# schematic.net
KiCad netlist of a schematic drawn in Altium Designer
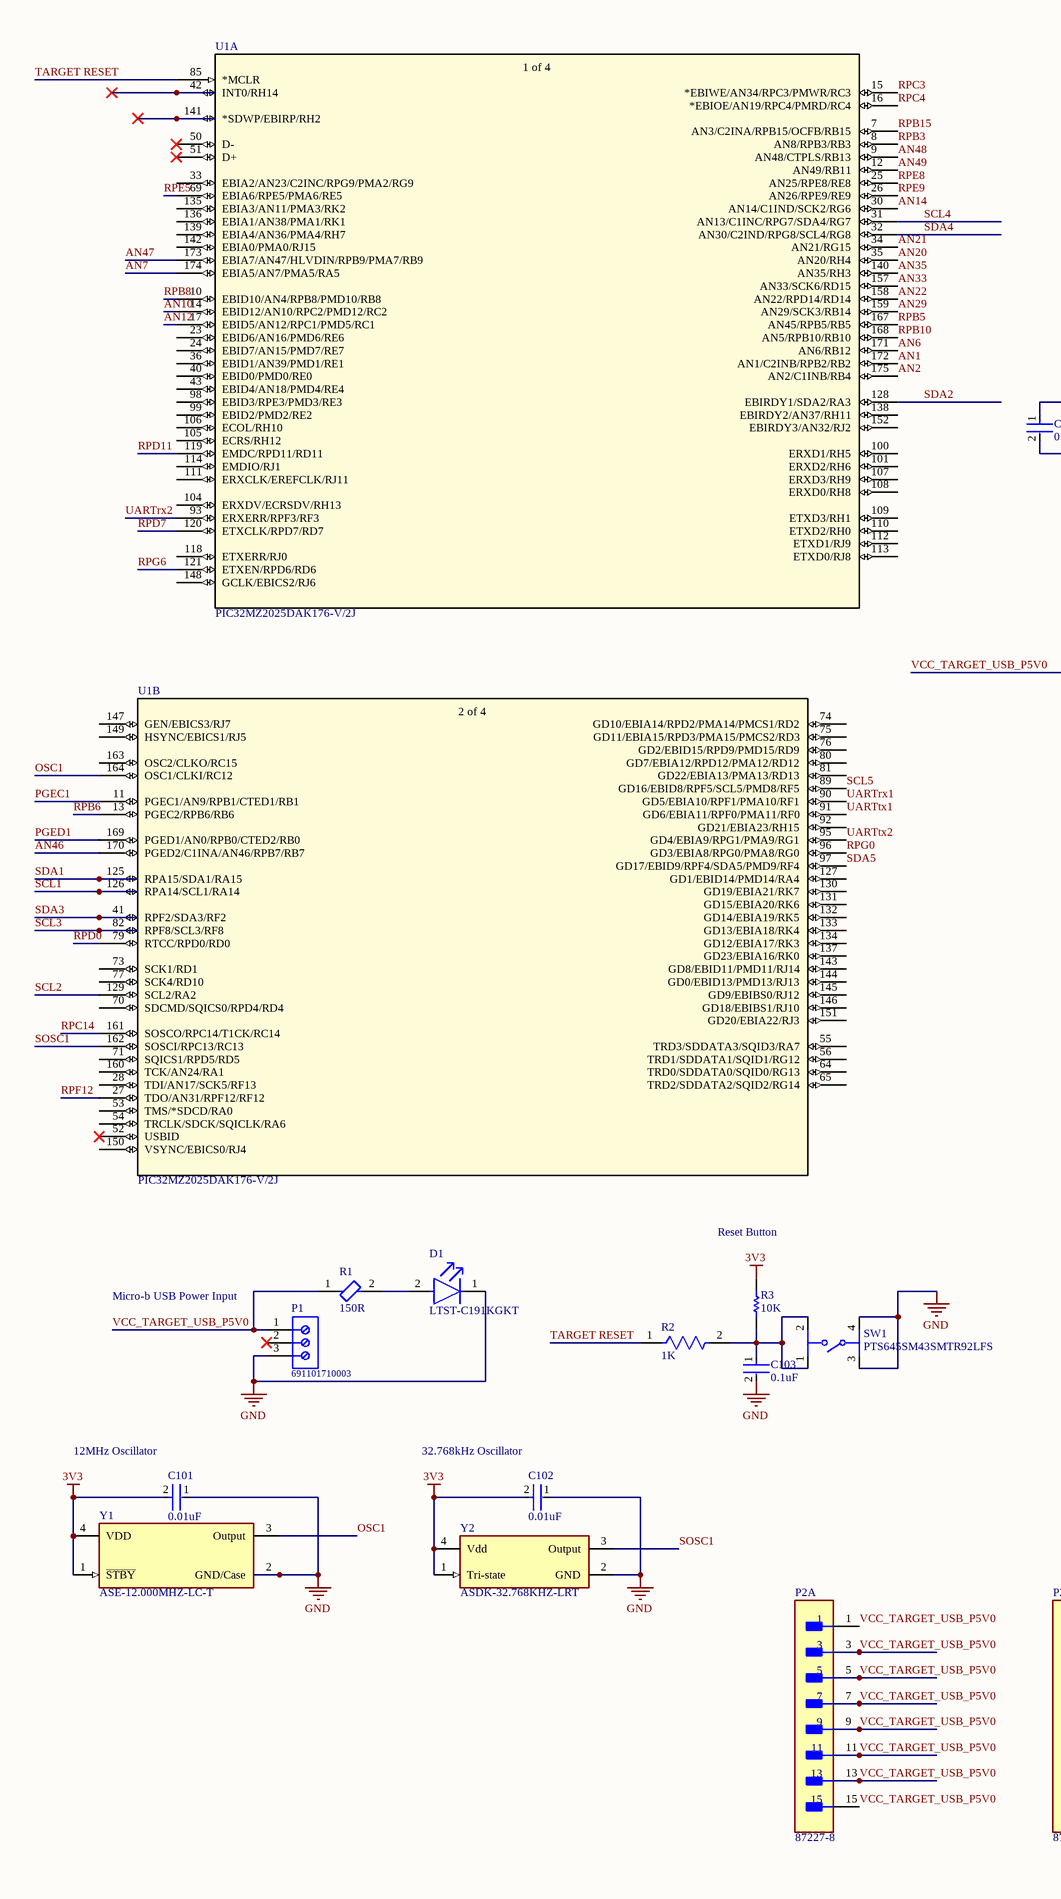
[diagram p0: schematic.SchDoc, left]
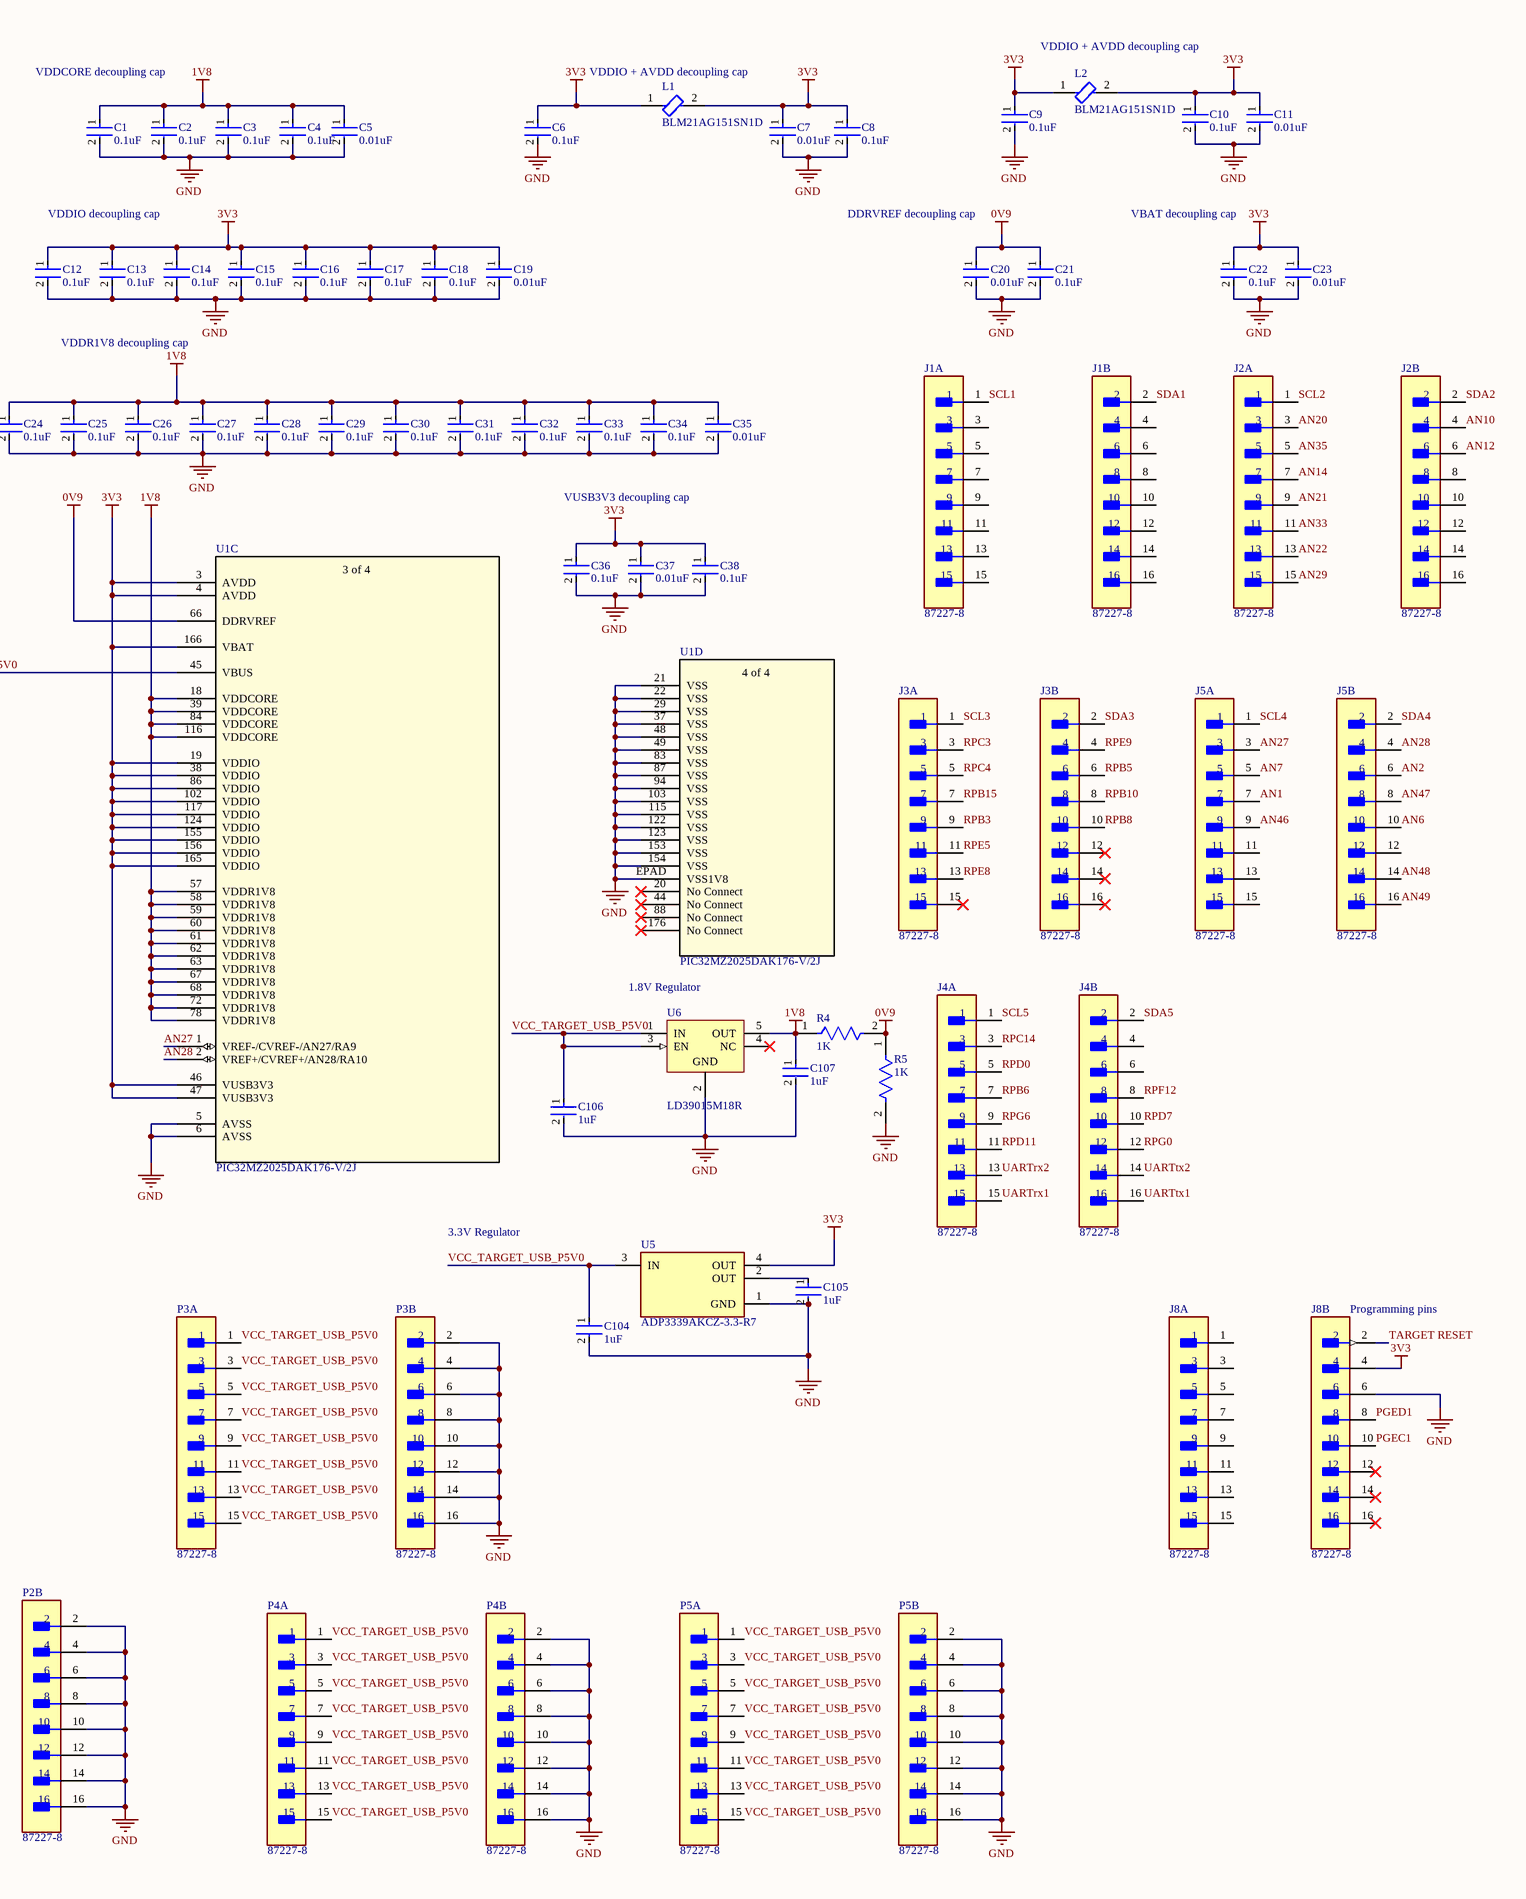
[diagram p1: schematic.SchDoc, right]

(export (version "E")
  (design (tool "Eeschema 10.0.6"))
  (components
    (comp (ref "C1")
      (value "0.1uF")
      (footprint "FP-CGA2B-MFG")
      (description "Cap Ceramic 100nF 50V X7R 10% Pad SMD 0402 +125°C Automotive T/R")
      (fields (field (name "VOLTAGE") "50V") (field (name "TOLERANCE") "10%"))
      (libsource (lib "Altium Content Vault") (part "b4654b650e69147ec39a6b967a45e02"))
    )
    (comp (ref "C2")
      (value "0.1uF")
      (footprint "FP-CGA2B-MFG")
      (description "Cap Ceramic 100nF 50V X7R 10% Pad SMD 0402 +125°C Automotive T/R")
      (fields (field (name "VOLTAGE") "50V") (field (name "TOLERANCE") "10%"))
      (libsource (lib "Altium Content Vault") (part "b4654b650e69147ec39a6b967a45e02"))
    )
    (comp (ref "C3")
      (value "0.1uF")
      (footprint "FP-CGA2B-MFG")
      (description "Cap Ceramic 100nF 50V X7R 10% Pad SMD 0402 +125°C Automotive T/R")
      (fields (field (name "VOLTAGE") "50V") (field (name "TOLERANCE") "10%"))
      (libsource (lib "Altium Content Vault") (part "b4654b650e69147ec39a6b967a45e02"))
    )
    (comp (ref "C4")
      (value "0.1uF")
      (footprint "FP-CGA2B-MFG")
      (description "Cap Ceramic 100nF 50V X7R 10% Pad SMD 0402 +125°C Automotive T/R")
      (fields (field (name "VOLTAGE") "50V") (field (name "TOLERANCE") "10%"))
      (libsource (lib "Altium Content Vault") (part "b4654b650e69147ec39a6b967a45e02"))
    )
    (comp (ref "C5")
      (value "0.01uF")
      (footprint "FP-C1005-050-0_05-IPC_B")
      (description "Multilayer Ceramic Capacitors 10nF ±20% 50V X5R SMD 0402")
      (fields (field (name "TOLERANCE") "20%"))
      (libsource (lib "Altium Content Vault") (part "b4654b650e69147ec39a6b967a45e02"))
    )
    (comp (ref "C6")
      (value "0.1uF")
      (footprint "FP-CGA2B-MFG")
      (description "Cap Ceramic 100nF 50V X7R 10% Pad SMD 0402 +125°C Automotive T/R")
      (fields (field (name "VOLTAGE") "50V") (field (name "TOLERANCE") "10%"))
      (libsource (lib "Altium Content Vault") (part "b4654b650e69147ec39a6b967a45e02"))
    )
    (comp (ref "C7")
      (value "0.01uF")
      (footprint "FP-C1005-050-0_05-IPC_B")
      (description "Multilayer Ceramic Capacitors 10nF ±20% 50V X5R SMD 0402")
      (fields (field (name "TOLERANCE") "20%"))
      (libsource (lib "Altium Content Vault") (part "b4654b650e69147ec39a6b967a45e02"))
    )
    (comp (ref "C8")
      (value "0.1uF")
      (footprint "FP-CGA2B-MFG")
      (description "Cap Ceramic 100nF 50V X7R 10% Pad SMD 0402 +125°C Automotive T/R")
      (fields (field (name "VOLTAGE") "50V") (field (name "TOLERANCE") "10%"))
      (libsource (lib "Altium Content Vault") (part "b4654b650e69147ec39a6b967a45e02"))
    )
    (comp (ref "C9")
      (value "0.1uF")
      (footprint "FP-CGA2B-MFG")
      (description "Cap Ceramic 100nF 50V X7R 10% Pad SMD 0402 +125°C Automotive T/R")
      (fields (field (name "VOLTAGE") "50V") (field (name "TOLERANCE") "10%"))
      (libsource (lib "Altium Content Vault") (part "b4654b650e69147ec39a6b967a45e02"))
    )
    (comp (ref "C10")
      (value "0.1uF")
      (footprint "FP-CGA2B-MFG")
      (description "Cap Ceramic 100nF 50V X7R 10% Pad SMD 0402 +125°C Automotive T/R")
      (fields (field (name "VOLTAGE") "50V") (field (name "TOLERANCE") "10%"))
      (libsource (lib "Altium Content Vault") (part "b4654b650e69147ec39a6b967a45e02"))
    )
    (comp (ref "C11")
      (value "0.01uF")
      (footprint "FP-C1005-050-0_05-IPC_B")
      (description "Multilayer Ceramic Capacitors 10nF ±20% 50V X5R SMD 0402")
      (fields (field (name "TOLERANCE") "20%"))
      (libsource (lib "Altium Content Vault") (part "b4654b650e69147ec39a6b967a45e02"))
    )
    (comp (ref "C12")
      (value "0.1uF")
      (footprint "FP-CGA2B-MFG")
      (description "Cap Ceramic 100nF 50V X7R 10% Pad SMD 0402 +125°C Automotive T/R")
      (fields (field (name "VOLTAGE") "50V") (field (name "TOLERANCE") "10%"))
      (libsource (lib "Altium Content Vault") (part "b4654b650e69147ec39a6b967a45e02"))
    )
    (comp (ref "C13")
      (value "0.1uF")
      (footprint "FP-CGA2B-MFG")
      (description "Cap Ceramic 100nF 50V X7R 10% Pad SMD 0402 +125°C Automotive T/R")
      (fields (field (name "VOLTAGE") "50V") (field (name "TOLERANCE") "10%"))
      (libsource (lib "Altium Content Vault") (part "b4654b650e69147ec39a6b967a45e02"))
    )
    (comp (ref "C14")
      (value "0.1uF")
      (footprint "FP-CGA2B-MFG")
      (description "Cap Ceramic 100nF 50V X7R 10% Pad SMD 0402 +125°C Automotive T/R")
      (fields (field (name "VOLTAGE") "50V") (field (name "TOLERANCE") "10%"))
      (libsource (lib "Altium Content Vault") (part "b4654b650e69147ec39a6b967a45e02"))
    )
    (comp (ref "C15")
      (value "0.1uF")
      (footprint "FP-CGA2B-MFG")
      (description "Cap Ceramic 100nF 50V X7R 10% Pad SMD 0402 +125°C Automotive T/R")
      (fields (field (name "VOLTAGE") "50V") (field (name "TOLERANCE") "10%"))
      (libsource (lib "Altium Content Vault") (part "b4654b650e69147ec39a6b967a45e02"))
    )
    (comp (ref "C16")
      (value "0.1uF")
      (footprint "FP-CGA2B-MFG")
      (description "Cap Ceramic 100nF 50V X7R 10% Pad SMD 0402 +125°C Automotive T/R")
      (fields (field (name "VOLTAGE") "50V") (field (name "TOLERANCE") "10%"))
      (libsource (lib "Altium Content Vault") (part "b4654b650e69147ec39a6b967a45e02"))
    )
    (comp (ref "C17")
      (value "0.1uF")
      (footprint "FP-CGA2B-MFG")
      (description "Cap Ceramic 100nF 50V X7R 10% Pad SMD 0402 +125°C Automotive T/R")
      (fields (field (name "VOLTAGE") "50V") (field (name "TOLERANCE") "10%"))
      (libsource (lib "Altium Content Vault") (part "b4654b650e69147ec39a6b967a45e02"))
    )
    (comp (ref "C18")
      (value "0.1uF")
      (footprint "FP-CGA2B-MFG")
      (description "Cap Ceramic 100nF 50V X7R 10% Pad SMD 0402 +125°C Automotive T/R")
      (fields (field (name "VOLTAGE") "50V") (field (name "TOLERANCE") "10%"))
      (libsource (lib "Altium Content Vault") (part "b4654b650e69147ec39a6b967a45e02"))
    )
    (comp (ref "C19")
      (value "0.01uF")
      (footprint "FP-C1005-050-0_05-IPC_B")
      (description "Multilayer Ceramic Capacitors 10nF ±20% 50V X5R SMD 0402")
      (fields (field (name "TOLERANCE") "20%"))
      (libsource (lib "Altium Content Vault") (part "b4654b650e69147ec39a6b967a45e02"))
    )
    (comp (ref "C20")
      (value "0.01uF")
      (footprint "FP-C1005-050-0_05-IPC_B")
      (description "Multilayer Ceramic Capacitors 10nF ±20% 50V X5R SMD 0402")
      (fields (field (name "TOLERANCE") "20%"))
      (libsource (lib "Altium Content Vault") (part "b4654b650e69147ec39a6b967a45e02"))
    )
    (comp (ref "C21")
      (value "0.1uF")
      (footprint "FP-CGA2B-MFG")
      (description "Cap Ceramic 100nF 50V X7R 10% Pad SMD 0402 +125°C Automotive T/R")
      (fields (field (name "VOLTAGE") "50V") (field (name "TOLERANCE") "10%"))
      (libsource (lib "Altium Content Vault") (part "b4654b650e69147ec39a6b967a45e02"))
    )
    (comp (ref "C22")
      (value "0.1uF")
      (footprint "FP-CGA2B-MFG")
      (description "Cap Ceramic 100nF 50V X7R 10% Pad SMD 0402 +125°C Automotive T/R")
      (fields (field (name "VOLTAGE") "50V") (field (name "TOLERANCE") "10%"))
      (libsource (lib "Altium Content Vault") (part "b4654b650e69147ec39a6b967a45e02"))
    )
    (comp (ref "C23")
      (value "0.01uF")
      (footprint "FP-C1005-050-0_05-IPC_B")
      (description "Multilayer Ceramic Capacitors 10nF ±20% 50V X5R SMD 0402")
      (fields (field (name "TOLERANCE") "20%"))
      (libsource (lib "Altium Content Vault") (part "b4654b650e69147ec39a6b967a45e02"))
    )
    (comp (ref "C24")
      (value "0.1uF")
      (footprint "FP-CGA2B-MFG")
      (description "Cap Ceramic 100nF 50V X7R 10% Pad SMD 0402 +125°C Automotive T/R")
      (fields (field (name "VOLTAGE") "50V") (field (name "TOLERANCE") "10%"))
      (libsource (lib "Altium Content Vault") (part "b4654b650e69147ec39a6b967a45e02"))
    )
    (comp (ref "C25")
      (value "0.1uF")
      (footprint "FP-CGA2B-MFG")
      (description "Cap Ceramic 100nF 50V X7R 10% Pad SMD 0402 +125°C Automotive T/R")
      (fields (field (name "VOLTAGE") "50V") (field (name "TOLERANCE") "10%"))
      (libsource (lib "Altium Content Vault") (part "b4654b650e69147ec39a6b967a45e02"))
    )
    (comp (ref "C26")
      (value "0.1uF")
      (footprint "FP-CGA2B-MFG")
      (description "Cap Ceramic 100nF 50V X7R 10% Pad SMD 0402 +125°C Automotive T/R")
      (fields (field (name "VOLTAGE") "50V") (field (name "TOLERANCE") "10%"))
      (libsource (lib "Altium Content Vault") (part "b4654b650e69147ec39a6b967a45e02"))
    )
    (comp (ref "C27")
      (value "0.1uF")
      (footprint "FP-CGA2B-MFG")
      (description "Cap Ceramic 100nF 50V X7R 10% Pad SMD 0402 +125°C Automotive T/R")
      (fields (field (name "VOLTAGE") "50V") (field (name "TOLERANCE") "10%"))
      (libsource (lib "Altium Content Vault") (part "b4654b650e69147ec39a6b967a45e02"))
    )
    (comp (ref "C28")
      (value "0.1uF")
      (footprint "FP-CGA2B-MFG")
      (description "Cap Ceramic 100nF 50V X7R 10% Pad SMD 0402 +125°C Automotive T/R")
      (fields (field (name "VOLTAGE") "50V") (field (name "TOLERANCE") "10%"))
      (libsource (lib "Altium Content Vault") (part "b4654b650e69147ec39a6b967a45e02"))
    )
    (comp (ref "C29")
      (value "0.1uF")
      (footprint "FP-CGA2B-MFG")
      (description "Cap Ceramic 100nF 50V X7R 10% Pad SMD 0402 +125°C Automotive T/R")
      (fields (field (name "VOLTAGE") "50V") (field (name "TOLERANCE") "10%"))
      (libsource (lib "Altium Content Vault") (part "b4654b650e69147ec39a6b967a45e02"))
    )
    (comp (ref "C30")
      (value "0.1uF")
      (footprint "FP-CGA2B-MFG")
      (description "Cap Ceramic 100nF 50V X7R 10% Pad SMD 0402 +125°C Automotive T/R")
      (fields (field (name "VOLTAGE") "50V") (field (name "TOLERANCE") "10%"))
      (libsource (lib "Altium Content Vault") (part "b4654b650e69147ec39a6b967a45e02"))
    )
    (comp (ref "C31")
      (value "0.1uF")
      (footprint "FP-CGA2B-MFG")
      (description "Cap Ceramic 100nF 50V X7R 10% Pad SMD 0402 +125°C Automotive T/R")
      (fields (field (name "VOLTAGE") "50V") (field (name "TOLERANCE") "10%"))
      (libsource (lib "Altium Content Vault") (part "b4654b650e69147ec39a6b967a45e02"))
    )
    (comp (ref "C32")
      (value "0.1uF")
      (footprint "FP-CGA2B-MFG")
      (description "Cap Ceramic 100nF 50V X7R 10% Pad SMD 0402 +125°C Automotive T/R")
      (fields (field (name "VOLTAGE") "50V") (field (name "TOLERANCE") "10%"))
      (libsource (lib "Altium Content Vault") (part "b4654b650e69147ec39a6b967a45e02"))
    )
    (comp (ref "C33")
      (value "0.1uF")
      (footprint "FP-CGA2B-MFG")
      (description "Cap Ceramic 100nF 50V X7R 10% Pad SMD 0402 +125°C Automotive T/R")
      (fields (field (name "VOLTAGE") "50V") (field (name "TOLERANCE") "10%"))
      (libsource (lib "Altium Content Vault") (part "b4654b650e69147ec39a6b967a45e02"))
    )
    (comp (ref "C34")
      (value "0.1uF")
      (footprint "FP-CGA2B-MFG")
      (description "Cap Ceramic 100nF 50V X7R 10% Pad SMD 0402 +125°C Automotive T/R")
      (fields (field (name "VOLTAGE") "50V") (field (name "TOLERANCE") "10%"))
      (libsource (lib "Altium Content Vault") (part "b4654b650e69147ec39a6b967a45e02"))
    )
    (comp (ref "C35")
      (value "0.01uF")
      (footprint "FP-C1005-050-0_05-IPC_B")
      (description "Multilayer Ceramic Capacitors 10nF ±20% 50V X5R SMD 0402")
      (fields (field (name "TOLERANCE") "20%"))
      (libsource (lib "Altium Content Vault") (part "b4654b650e69147ec39a6b967a45e02"))
    )
    (comp (ref "C36")
      (value "0.1uF")
      (footprint "FP-CGA2B-MFG")
      (description "Cap Ceramic 100nF 50V X7R 10% Pad SMD 0402 +125°C Automotive T/R")
      (fields (field (name "VOLTAGE") "50V") (field (name "TOLERANCE") "10%"))
      (libsource (lib "Altium Content Vault") (part "b4654b650e69147ec39a6b967a45e02"))
    )
    (comp (ref "C37")
      (value "0.01uF")
      (footprint "FP-C1005-050-0_05-IPC_B")
      (description "Multilayer Ceramic Capacitors 10nF ±20% 50V X5R SMD 0402")
      (fields (field (name "TOLERANCE") "20%"))
      (libsource (lib "Altium Content Vault") (part "b4654b650e69147ec39a6b967a45e02"))
    )
    (comp (ref "C38")
      (value "0.1uF")
      (footprint "FP-CGA2B-MFG")
      (description "Cap Ceramic 100nF 50V X7R 10% Pad SMD 0402 +125°C Automotive T/R")
      (fields (field (name "VOLTAGE") "50V") (field (name "TOLERANCE") "10%"))
      (libsource (lib "Altium Content Vault") (part "b4654b650e69147ec39a6b967a45e02"))
    )
    (comp (ref "C101")
      (value "0.01uF")
      (footprint "FP-C1608-080-0_1-MFG")
      (description "Multilayer Ceramic Capacitors 10nF ±10% 50V X7R SMD 0603")
      (fields (field (name "VOLTAGE") "50V") (field (name "TOLERANCE") "10%"))
      (libsource (lib "Altium Content Vault") (part "236180d848d6139a670b325ea6854c9"))
    )
    (comp (ref "C102")
      (value "0.01uF")
      (footprint "FP-C1608-080-0_1-MFG")
      (description "Multilayer Ceramic Capacitors 10nF ±10% 50V X7R SMD 0603")
      (fields (field (name "VOLTAGE") "50V") (field (name "TOLERANCE") "10%"))
      (libsource (lib "Altium Content Vault") (part "236180d848d6139a670b325ea6854c9"))
    )
    (comp (ref "C103")
      (value "0.1uF")
      (footprint "FP-CGA3E-0_3-0_1-IPC_A")
      (description "Cap Ceramic 100nF 50V X7R 10% Pad SMD 0603 +125°C Automotive T/R")
      (fields (field (name "TOLERANCE") "10%") (field (name "VOLTAGE") "50V"))
      (libsource (lib "Altium Content Vault") (part "b4654b650e69147ec39a6b967a45e02"))
    )
    (comp (ref "C104")
      (value "1uF")
      (footprint "FP-0603-L_1_6_0_1-W_0_8_0-IPC_B")
      (description "None")
      (fields (field (name "TOLERANCE") "10%"))
      (libsource (lib "Altium Content Vault") (part "02cd4be3c70576c341d710602a673aa"))
    )
    (comp (ref "C105")
      (value "1uF")
      (footprint "FP-0603-L_1_6_0_1-W_0_8_0-IPC_B")
      (description "None")
      (fields (field (name "TOLERANCE") "10%"))
      (libsource (lib "Altium Content Vault") (part "02cd4be3c70576c341d710602a673aa"))
    )
    (comp (ref "C106")
      (value "1uF")
      (footprint "FP-0603-L_1_6_0_1-W_0_8_0-IPC_B")
      (description "None")
      (fields (field (name "TOLERANCE") "10%"))
      (libsource (lib "Altium Content Vault") (part "02cd4be3c70576c341d710602a673aa"))
    )
    (comp (ref "C107")
      (value "1uF")
      (footprint "FP-0603-L_1_6_0_1-W_0_8_0-IPC_B")
      (description "None")
      (fields (field (name "TOLERANCE") "10%"))
      (libsource (lib "Altium Content Vault") (part "02cd4be3c70576c341d710602a673aa"))
    )
    (comp (ref "D1")
      (value "LTST-C191KGKT")
      (footprint "FP-LTST-C191KGKT-MFG")
      (description "LED GREEN CLEAR SMD")
      (libsource (lib "Altium Content Vault") (part "8706943c75ba83719d021d2fdc84c58"))
    )
    (comp (ref "J1")
      (value "87227-8")
      (footprint "FP-87227-8-MFG")
      (description "CONN HEADER VERT 16POS 2.54MM")
      (fields
        (field (name "MANUFACTURER") "TE Connectivity")
        (field (name "OCTOPART") "https://octopart.com/87227-8-te+connectivity-39407754")
      )
      (libsource (lib "Altium Content Vault") (part "4b6d22b45e2f925f038cba5d936fbcc"))
    )
    (comp (ref "J2")
      (value "87227-8")
      (footprint "FP-87227-8-MFG")
      (description "CONN HEADER VERT 16POS 2.54MM")
      (fields
        (field (name "MANUFACTURER") "TE Connectivity")
        (field (name "OCTOPART") "https://octopart.com/87227-8-te+connectivity-39407754")
      )
      (libsource (lib "Altium Content Vault") (part "4b6d22b45e2f925f038cba5d936fbcc"))
    )
    (comp (ref "J3")
      (value "87227-8")
      (footprint "FP-87227-8-MFG")
      (description "CONN HEADER VERT 16POS 2.54MM")
      (fields
        (field (name "MANUFACTURER") "TE Connectivity")
        (field (name "OCTOPART") "https://octopart.com/87227-8-te+connectivity-39407754")
      )
      (libsource (lib "Altium Content Vault") (part "4b6d22b45e2f925f038cba5d936fbcc"))
    )
    (comp (ref "J4")
      (value "87227-8")
      (footprint "FP-87227-8-MFG")
      (description "CONN HEADER VERT 16POS 2.54MM")
      (fields
        (field (name "MANUFACTURER") "TE Connectivity")
        (field (name "OCTOPART") "https://octopart.com/87227-8-te+connectivity-39407754")
      )
      (libsource (lib "Altium Content Vault") (part "4b6d22b45e2f925f038cba5d936fbcc"))
    )
    (comp (ref "J5")
      (value "87227-8")
      (footprint "FP-87227-8-MFG")
      (description "CONN HEADER VERT 16POS 2.54MM")
      (fields
        (field (name "MANUFACTURER") "TE Connectivity")
        (field (name "OCTOPART") "https://octopart.com/87227-8-te+connectivity-39407754")
      )
      (libsource (lib "Altium Content Vault") (part "4b6d22b45e2f925f038cba5d936fbcc"))
    )
    (comp (ref "J8")
      (value "87227-8")
      (footprint "FP-87227-8-MFG")
      (description "CONN HEADER VERT 16POS 2.54MM")
      (fields
        (field (name "MANUFACTURER") "TE Connectivity")
        (field (name "OCTOPART") "https://octopart.com/87227-8-te+connectivity-39407754")
      )
      (libsource (lib "Altium Content Vault") (part "4b6d22b45e2f925f038cba5d936fbcc"))
    )
    (comp (ref "L1")
      (value "BLM21AG151SN1D")
      (footprint "FP-BLM21-0_2-t0_85-e0_5-MFG")
      (description "Chip Ferrite Bead, 0805, 150Ω @ 100MHz, 0.09Ω, 25%, 1A")
      (fields (field (name "TOLERANCE") "25%"))
      (libsource (lib "Altium Content Vault") (part "5f30dd21d616792df468990f7003faa"))
    )
    (comp (ref "L2")
      (value "BLM21AG151SN1D")
      (footprint "FP-BLM21-0_2-t0_85-e0_5-MFG")
      (description "Chip Ferrite Bead, 0805, 150Ω @ 100MHz, 0.09Ω, 25%, 1A")
      (fields (field (name "TOLERANCE") "25%"))
      (libsource (lib "Altium Content Vault") (part "5f30dd21d616792df468990f7003faa"))
    )
    (comp (ref "P1")
      (value "691101710003")
      (footprint "691101710003")
      (description "Series 101 - 5.00 mm Horizontal Entry Modular with Pressure Clamp WR-TBL, 3 pin")
      (fields (field (name "MANUFACTURER") "Wurth Elektronik") (field (name "PUBLISHER") "WurthElektronik"))
      (libsource (lib "Altium Content Vault") (part "WE-CN-1P-F-TB3"))
    )
    (comp (ref "P2")
      (value "87227-8")
      (footprint "FP-87227-8-MFG")
      (description "CONN HEADER VERT 16POS 2.54MM")
      (fields
        (field (name "MANUFACTURER") "TE Connectivity")
        (field (name "OCTOPART") "https://octopart.com/87227-8-te+connectivity-39407754")
      )
      (libsource (lib "Altium Content Vault") (part "4b6d22b45e2f925f038cba5d936fbcc"))
    )
    (comp (ref "P3")
      (value "87227-8")
      (footprint "FP-87227-8-MFG")
      (description "CONN HEADER VERT 16POS 2.54MM")
      (fields
        (field (name "MANUFACTURER") "TE Connectivity")
        (field (name "OCTOPART") "https://octopart.com/87227-8-te+connectivity-39407754")
      )
      (libsource (lib "Altium Content Vault") (part "4b6d22b45e2f925f038cba5d936fbcc"))
    )
    (comp (ref "P4")
      (value "87227-8")
      (footprint "FP-87227-8-MFG")
      (description "CONN HEADER VERT 16POS 2.54MM")
      (fields
        (field (name "MANUFACTURER") "TE Connectivity")
        (field (name "OCTOPART") "https://octopart.com/87227-8-te+connectivity-39407754")
      )
      (libsource (lib "Altium Content Vault") (part "4b6d22b45e2f925f038cba5d936fbcc"))
    )
    (comp (ref "P5")
      (value "87227-8")
      (footprint "FP-87227-8-MFG")
      (description "CONN HEADER VERT 16POS 2.54MM")
      (fields
        (field (name "MANUFACTURER") "TE Connectivity")
        (field (name "OCTOPART") "https://octopart.com/87227-8-te+connectivity-39407754")
      )
      (libsource (lib "Altium Content Vault") (part "4b6d22b45e2f925f038cba5d936fbcc"))
    )
    (comp (ref "R1")
      (value "150R")
      (footprint "FP-BLM18-0_15-t0_8-IPC_B")
      (description "Chip Ferrite Bead, 0603, 150Ω @ 100MHz, 0.4Ω, 25%, 300mA")
      (fields (field (name "TOLERANCE") "25%"))
      (libsource (lib "Altium Content Vault") (part "5f30dd21d616792df468990f7003faa"))
    )
    (comp (ref "R2")
      (value "1K")
      (footprint "FP-ERJ3G-MFG")
      (description "RES SMD 1K OHM 5% 1/10W 0603")
      (fields (field (name "VOLTAGE") "75 V") (field (name "MANUFACTURER") "Panasonic"))
      (libsource (lib "Altium Content Vault") (part "1029c3af85768c4190bb7ad29bc67b5"))
    )
    (comp (ref "R3")
      (value "10K")
      (footprint "RESC1609X55X30LL15T15")
      (description "Chip Resistor, 10 KOhm, +/- 1%, 0.1 W, -55 to 155 degC, 0603 (1608 Metric), RoHS, Tape and Reel")
      (fields (field (name "TOLERANCE") "1%") (field (name "MANUFACTURER") "Panasonic"))
      (libsource (lib "Altium Content Vault") (part "RES-2"))
    )
    (comp (ref "R4")
      (value "1K")
      (footprint "FP-ERJ3G-MFG")
      (description "RES SMD 1K OHM 5% 1/10W 0603")
      (fields (field (name "VOLTAGE") "75 V") (field (name "MANUFACTURER") "Panasonic"))
      (libsource (lib "Altium Content Vault") (part "1029c3af85768c4190bb7ad29bc67b5"))
    )
    (comp (ref "R5")
      (value "1K")
      (footprint "FP-ERJ3G-MFG")
      (description "RES SMD 1K OHM 5% 1/10W 0603")
      (fields (field (name "VOLTAGE") "75 V") (field (name "MANUFACTURER") "Panasonic"))
      (libsource (lib "Altium Content Vault") (part "1029c3af85768c4190bb7ad29bc67b5"))
    )
    (comp (ref "SW1")
      (value "PTS645SM43SMTR92LFS")
      (footprint "FP-PTS645SM43SMTR92LFS-MFG")
      (description "SWITCH TACTILE SPST-NO 0.05A 12V")
      (libsource (lib "Altium Content Vault") (part "1adf0dd01260c80cf25a44bfd6b99ba"))
    )
    (comp (ref "U1")
      (value "PIC32MZ2025DAK176-V/2J")
      (footprint "LQFP176_2J_MCH")
      (description "No Description Available")
      (fields (field (name "COPYRIGHT") "Copyright (C) 2022 Ultra Librarian. All rights reserved."))
      (libsource (lib "PIC32MZ2025DAK176-V&slash_2J") (part "PIC32MZ2025DAK176-V/2J"))
    )
    (comp (ref "U5")
      (value "ADP3339AKCZ-3.3-R7")
      (footprint "FP-KC-3-IPC_C")
      (description "IC REG LINEAR 3.3V 1.5A SOT223-3")
      (libsource (lib "Altium Content Vault") (part "9a28c78e4705cf0ec0890e31d7bbefd"))
    )
    (comp (ref "U6")
      (value "LD39015M18R")
      (footprint "SOT23-5L_M")
      (description "150 mA Low Quiescent Current Low Noise Voltage Regulator, 1.8V, 5-Pin SOT-23, Tape and Reel")
      (libsource (lib "Altium Content Vault") (part "PM-REG-LD39015M-SOT5"))
    )
    (comp (ref "Y1")
      (value "ASE-12.000MHZ-LC-T")
      (footprint "FP-ASE-MFG")
      (description "XTAL Oscillator 12MHz ±50ppm CMOS 3.3V 4-SMD 3.2mm x 2.5mm")
      (libsource (lib "Altium Content Vault") (part "61a724e6190563596ac712fef61ad37"))
    )
    (comp (ref "Y2")
      (value "ASDK-32.768KHZ-LRT")
      (footprint "FP-ASDK-MFG")
      (description "XTAL OSC XO 32.7680KHZ CMOS SMD")
      (libsource (lib "Altium Content Vault") (part "a7425352bb6ebc83bfd0f12a23808e7"))
    )
  )
  (nets
    (net (code "1") (name "/AN1") (class "Default")
      (node (ref "J5") (pin "7") (pinfunction "7_7") (pintype "passive"))
      (node (ref "U1") (pin "172") (pinfunction "AN1/C2INB/RPB2/RB2_172") (pintype "bidirectional"))
    )
    (net (code "2") (name "/AN2") (class "Default")
      (node (ref "J5") (pin "6") (pinfunction "6_6") (pintype "passive"))
      (node (ref "U1") (pin "175") (pinfunction "AN2/C1INB/RB4_175") (pintype "bidirectional"))
    )
    (net (code "3") (name "/AN6") (class "Default")
      (node (ref "J5") (pin "10") (pinfunction "10_10") (pintype "passive"))
      (node (ref "U1") (pin "171") (pinfunction "AN6/RB12_171") (pintype "bidirectional"))
    )
    (net (code "4") (name "/AN7") (class "Default")
      (node (ref "J5") (pin "5") (pinfunction "5_5") (pintype "passive"))
      (node (ref "U1") (pin "174") (pinfunction "EBIA5/AN7/PMA5/RA5_174") (pintype "bidirectional"))
    )
    (net (code "5") (name "/AN10") (class "Default")
      (node (ref "J2") (pin "4") (pinfunction "4_4") (pintype "passive"))
      (node (ref "U1") (pin "14") (pinfunction "EBID12/AN10/RPC2/PMD12/RC2_14") (pintype "bidirectional"))
    )
    (net (code "6") (name "/AN12") (class "Default")
      (node (ref "J2") (pin "6") (pinfunction "6_6") (pintype "passive"))
      (node (ref "U1") (pin "17") (pinfunction "EBID5/AN12/RPC1/PMD5/RC1_17") (pintype "bidirectional"))
    )
    (net (code "7") (name "/AN14") (class "Default")
      (node (ref "J2") (pin "7") (pinfunction "7_7") (pintype "passive"))
      (node (ref "U1") (pin "30") (pinfunction "AN14/C1IND/SCK2/RG6_30") (pintype "bidirectional"))
    )
    (net (code "8") (name "/AN20") (class "Default")
      (node (ref "J2") (pin "3") (pinfunction "3_3") (pintype "passive"))
      (node (ref "U1") (pin "35") (pinfunction "AN20/RH4_35") (pintype "bidirectional"))
    )
    (net (code "9") (name "/AN21") (class "Default")
      (node (ref "J2") (pin "9") (pinfunction "9_9") (pintype "passive"))
      (node (ref "U1") (pin "34") (pinfunction "AN21/RG15_34") (pintype "bidirectional"))
    )
    (net (code "10") (name "/AN22") (class "Default")
      (node (ref "J2") (pin "13") (pinfunction "13_13") (pintype "passive"))
      (node (ref "U1") (pin "158") (pinfunction "AN22/RPD14/RD14_158") (pintype "bidirectional"))
    )
    (net (code "11") (name "/AN27") (class "Default")
      (node (ref "J5") (pin "3") (pinfunction "3_3") (pintype "passive"))
      (node (ref "U1") (pin "1") (pinfunction "VREF-/CVREF-/AN27/RA9_1") (pintype "bidirectional"))
    )
    (net (code "12") (name "/AN28") (class "Default")
      (node (ref "J5") (pin "4") (pinfunction "4_4") (pintype "passive"))
      (node (ref "U1") (pin "2") (pinfunction "VREF+/CVREF+/AN28/RA10_2") (pintype "bidirectional"))
    )
    (net (code "13") (name "/AN29") (class "Default")
      (node (ref "J2") (pin "15") (pinfunction "15_15") (pintype "passive"))
      (node (ref "U1") (pin "159") (pinfunction "AN29/SCK3/RB14_159") (pintype "bidirectional"))
    )
    (net (code "14") (name "/AN33") (class "Default")
      (node (ref "J2") (pin "11") (pinfunction "11_11") (pintype "passive"))
      (node (ref "U1") (pin "157") (pinfunction "AN33/SCK6/RD15_157") (pintype "bidirectional"))
    )
    (net (code "15") (name "/AN35") (class "Default")
      (node (ref "J2") (pin "5") (pinfunction "5_5") (pintype "passive"))
      (node (ref "U1") (pin "140") (pinfunction "AN35/RH3_140") (pintype "bidirectional"))
    )
    (net (code "16") (name "/AN46") (class "Default")
      (node (ref "J5") (pin "9") (pinfunction "9_9") (pintype "passive"))
      (node (ref "U1") (pin "170") (pinfunction "PGED2/C1INA/AN46/RPB7/RB7_170") (pintype "bidirectional"))
    )
    (net (code "17") (name "/AN47") (class "Default")
      (node (ref "J5") (pin "8") (pinfunction "8_8") (pintype "passive"))
      (node (ref "U1") (pin "173") (pinfunction "EBIA7/AN47/HLVDIN/RPB9/PMA7/RB9_173") (pintype "bidirectional"))
    )
    (net (code "18") (name "/AN48") (class "Default")
      (node (ref "J5") (pin "14") (pinfunction "14_14") (pintype "passive"))
      (node (ref "U1") (pin "9") (pinfunction "AN48/CTPLS/RB13_9") (pintype "bidirectional"))
    )
    (net (code "19") (name "/AN49") (class "Default")
      (node (ref "J5") (pin "16") (pinfunction "16_16") (pintype "passive"))
      (node (ref "U1") (pin "12") (pinfunction "AN49/RB11_12") (pintype "bidirectional"))
    )
    (net (code "20") (name "/OSC1") (class "Default")
      (node (ref "U1") (pin "164") (pinfunction "OSC1/CLKI/RC12_164") (pintype "bidirectional"))
      (node (ref "Y1") (pin "3") (pinfunction "Output_3") (pintype "passive"))
    )
    (net (code "21") (name "/PGEC1") (class "Default")
      (node (ref "J8") (pin "10") (pinfunction "10_10") (pintype "passive"))
      (node (ref "U1") (pin "11") (pinfunction "PGEC1/AN9/RPB1/CTED1/RB1_11") (pintype "bidirectional"))
    )
    (net (code "22") (name "/PGED1") (class "Default")
      (node (ref "J8") (pin "8") (pinfunction "8_8") (pintype "passive"))
      (node (ref "U1") (pin "169") (pinfunction "PGED1/AN0/RPB0/CTED2/RB0_169") (pintype "bidirectional"))
    )
    (net (code "23") (name "/RPB3") (class "Default")
      (node (ref "J3") (pin "9") (pinfunction "9_9") (pintype "passive"))
      (node (ref "U1") (pin "8") (pinfunction "AN8/RPB3/RB3_8") (pintype "bidirectional"))
    )
    (net (code "24") (name "/RPB5") (class "Default")
      (node (ref "J3") (pin "6") (pinfunction "6_6") (pintype "passive"))
      (node (ref "U1") (pin "167") (pinfunction "AN45/RPB5/RB5_167") (pintype "bidirectional"))
    )
    (net (code "25") (name "/RPB6") (class "Default")
      (node (ref "J4") (pin "7") (pinfunction "7_7") (pintype "passive"))
      (node (ref "U1") (pin "13") (pinfunction "PGEC2/RPB6/RB6_13") (pintype "bidirectional"))
    )
    (net (code "26") (name "/RPB8") (class "Default")
      (node (ref "J3") (pin "10") (pinfunction "10_10") (pintype "passive"))
      (node (ref "U1") (pin "10") (pinfunction "EBID10/AN4/RPB8/PMD10/RB8_10") (pintype "bidirectional"))
    )
    (net (code "27") (name "/RPB10") (class "Default")
      (node (ref "J3") (pin "8") (pinfunction "8_8") (pintype "passive"))
      (node (ref "U1") (pin "168") (pinfunction "AN5/RPB10/RB10_168") (pintype "bidirectional"))
    )
    (net (code "28") (name "/RPB15") (class "Default")
      (node (ref "J3") (pin "7") (pinfunction "7_7") (pintype "passive"))
      (node (ref "U1") (pin "7") (pinfunction "AN3/C2INA/RPB15/OCFB/RB15_7") (pintype "bidirectional"))
    )
    (net (code "29") (name "/RPC3") (class "Default")
      (node (ref "J3") (pin "3") (pinfunction "3_3") (pintype "passive"))
      (node (ref "U1") (pin "15") (pinfunction "*EBIWE/AN34/RPC3/PMWR/RC3_15") (pintype "bidirectional"))
    )
    (net (code "30") (name "/RPC4") (class "Default")
      (node (ref "J3") (pin "5") (pinfunction "5_5") (pintype "passive"))
      (node (ref "U1") (pin "16") (pinfunction "*EBIOE/AN19/RPC4/PMRD/RC4_16") (pintype "bidirectional"))
    )
    (net (code "31") (name "/RPC14") (class "Default")
      (node (ref "J4") (pin "3") (pinfunction "3_3") (pintype "passive"))
      (node (ref "U1") (pin "161") (pinfunction "SOSCO/RPC14/T1CK/RC14_161") (pintype "bidirectional"))
    )
    (net (code "32") (name "/RPD0") (class "Default")
      (node (ref "J4") (pin "5") (pinfunction "5_5") (pintype "passive"))
      (node (ref "U1") (pin "79") (pinfunction "RTCC/RPD0/RD0_79") (pintype "bidirectional"))
    )
    (net (code "33") (name "/RPD7") (class "Default")
      (node (ref "J4") (pin "10") (pinfunction "10_10") (pintype "passive"))
      (node (ref "U1") (pin "120") (pinfunction "ETXCLK/RPD7/RD7_120") (pintype "bidirectional"))
    )
    (net (code "34") (name "/RPD11") (class "Default")
      (node (ref "J4") (pin "11") (pinfunction "11_11") (pintype "passive"))
      (node (ref "U1") (pin "119") (pinfunction "EMDC/RPD11/RD11_119") (pintype "bidirectional"))
    )
    (net (code "35") (name "/RPE5") (class "Default")
      (node (ref "J3") (pin "11") (pinfunction "11_11") (pintype "passive"))
      (node (ref "U1") (pin "69") (pinfunction "EBIA6/RPE5/PMA6/RE5_69") (pintype "bidirectional"))
    )
    (net (code "36") (name "/RPE8") (class "Default")
      (node (ref "J3") (pin "13") (pinfunction "13_13") (pintype "passive"))
      (node (ref "U1") (pin "25") (pinfunction "AN25/RPE8/RE8_25") (pintype "bidirectional"))
    )
    (net (code "37") (name "/RPE9") (class "Default")
      (node (ref "J3") (pin "4") (pinfunction "4_4") (pintype "passive"))
      (node (ref "U1") (pin "26") (pinfunction "AN26/RPE9/RE9_26") (pintype "bidirectional"))
    )
    (net (code "38") (name "/RPF12") (class "Default")
      (node (ref "J4") (pin "8") (pinfunction "8_8") (pintype "passive"))
      (node (ref "U1") (pin "27") (pinfunction "TDO/AN31/RPF12/RF12_27") (pintype "bidirectional"))
    )
    (net (code "39") (name "/RPG0") (class "Default")
      (node (ref "J4") (pin "12") (pinfunction "12_12") (pintype "passive"))
      (node (ref "U1") (pin "96") (pinfunction "GD3/EBIA8/RPG0/PMA8/RG0_96") (pintype "bidirectional"))
    )
    (net (code "40") (name "/RPG6") (class "Default")
      (node (ref "J4") (pin "9") (pinfunction "9_9") (pintype "passive"))
      (node (ref "U1") (pin "121") (pinfunction "ETXEN/RPD6/RD6_121") (pintype "bidirectional"))
    )
    (net (code "41") (name "/SCL1") (class "Default")
      (node (ref "J1") (pin "1") (pinfunction "1_1") (pintype "passive"))
      (node (ref "U1") (pin "126") (pinfunction "RPA14/SCL1/RA14_126") (pintype "bidirectional"))
    )
    (net (code "42") (name "/SCL2") (class "Default")
      (node (ref "J2") (pin "1") (pinfunction "1_1") (pintype "passive"))
      (node (ref "U1") (pin "129") (pinfunction "SCL2/RA2_129") (pintype "bidirectional"))
    )
    (net (code "43") (name "/SCL3") (class "Default")
      (node (ref "J3") (pin "1") (pinfunction "1_1") (pintype "passive"))
      (node (ref "U1") (pin "82") (pinfunction "RPF8/SCL3/RF8_82") (pintype "bidirectional"))
    )
    (net (code "44") (name "/SCL4") (class "Default")
      (node (ref "J5") (pin "1") (pinfunction "1_1") (pintype "passive"))
      (node (ref "U1") (pin "31") (pinfunction "AN13/C1INC/RPG7/SDA4/RG7_31") (pintype "bidirectional"))
    )
    (net (code "45") (name "/SCL5") (class "Default")
      (node (ref "J4") (pin "1") (pinfunction "1_1") (pintype "passive"))
      (node (ref "U1") (pin "89") (pinfunction "GD16/EBID8/RPF5/SCL5/PMD8/RF5_89") (pintype "bidirectional"))
    )
    (net (code "46") (name "/SDA1") (class "Default")
      (node (ref "J1") (pin "2") (pinfunction "2_2") (pintype "passive"))
      (node (ref "U1") (pin "125") (pinfunction "RPA15/SDA1/RA15_125") (pintype "bidirectional"))
    )
    (net (code "47") (name "/SDA2") (class "Default")
      (node (ref "J2") (pin "2") (pinfunction "2_2") (pintype "passive"))
      (node (ref "U1") (pin "128") (pinfunction "EBIRDY1/SDA2/RA3_128") (pintype "bidirectional"))
    )
    (net (code "48") (name "/SDA3") (class "Default")
      (node (ref "J3") (pin "2") (pinfunction "2_2") (pintype "passive"))
      (node (ref "U1") (pin "41") (pinfunction "RPF2/SDA3/RF2_41") (pintype "bidirectional"))
    )
    (net (code "49") (name "/SDA4") (class "Default")
      (node (ref "J5") (pin "2") (pinfunction "2_2") (pintype "passive"))
      (node (ref "U1") (pin "32") (pinfunction "AN30/C2IND/RPG8/SCL4/RG8_32") (pintype "bidirectional"))
    )
    (net (code "50") (name "/SDA5") (class "Default")
      (node (ref "J4") (pin "2") (pinfunction "2_2") (pintype "passive"))
      (node (ref "U1") (pin "97") (pinfunction "GD17/EBID9/RPF4/SDA5/PMD9/RF4_97") (pintype "bidirectional"))
    )
    (net (code "51") (name "/SOSC1") (class "Default")
      (node (ref "U1") (pin "162") (pinfunction "SOSCI/RPC13/RC13_162") (pintype "bidirectional"))
      (node (ref "Y2") (pin "3") (pinfunction "Output_3") (pintype "tri_state"))
    )
    (net (code "52") (name "/TARGET RESET") (class "Default")
      (node (ref "J8") (pin "2") (pinfunction "2_2") (pintype "passive"))
      (node (ref "R2") (pin "1") (pinfunction "1_1") (pintype "passive"))
      (node (ref "U1") (pin "85") (pinfunction "*MCLR_85") (pintype "input"))
    )
    (net (code "53") (name "/UARTrx1") (class "Default")
      (node (ref "J4") (pin "15") (pinfunction "15_15") (pintype "passive"))
      (node (ref "U1") (pin "90") (pinfunction "GD5/EBIA10/RPF1/PMA10/RF1_90") (pintype "bidirectional"))
    )
    (net (code "54") (name "/UARTrx2") (class "Default")
      (node (ref "J4") (pin "13") (pinfunction "13_13") (pintype "passive"))
      (node (ref "U1") (pin "93") (pinfunction "ERXERR/RPF3/RF3_93") (pintype "bidirectional"))
    )
    (net (code "55") (name "/UARTtx1") (class "Default")
      (node (ref "J4") (pin "16") (pinfunction "16_16") (pintype "passive"))
      (node (ref "U1") (pin "91") (pinfunction "GD6/EBIA11/RPF0/PMA11/RF0_91") (pintype "bidirectional"))
    )
    (net (code "56") (name "/UARTtx2") (class "Default")
      (node (ref "J4") (pin "14") (pinfunction "14_14") (pintype "passive"))
      (node (ref "U1") (pin "95") (pinfunction "GD4/EBIA9/RPG1/PMA9/RG1_95") (pintype "bidirectional"))
    )
    (net (code "57") (name "/VCC_TARGET_USB_P5V0") (class "Default")
      (node (ref "C104") (pin "1") (pinfunction "1_1") (pintype "passive"))
      (node (ref "C106") (pin "1") (pinfunction "1_1") (pintype "passive"))
      (node (ref "P1") (pin "1") (pinfunction "1_1") (pintype "passive"))
      (node (ref "P2") (pin "1") (pinfunction "1_1") (pintype "passive"))
      (node (ref "P2") (pin "11") (pinfunction "11_11") (pintype "passive"))
      (node (ref "P2") (pin "13") (pinfunction "13_13") (pintype "passive"))
      (node (ref "P2") (pin "15") (pinfunction "15_15") (pintype "passive"))
      (node (ref "P2") (pin "3") (pinfunction "3_3") (pintype "passive"))
      (node (ref "P2") (pin "5") (pinfunction "5_5") (pintype "passive"))
      (node (ref "P2") (pin "7") (pinfunction "7_7") (pintype "passive"))
      (node (ref "P2") (pin "9") (pinfunction "9_9") (pintype "passive"))
      (node (ref "P3") (pin "1") (pinfunction "1_1") (pintype "passive"))
      (node (ref "P3") (pin "11") (pinfunction "11_11") (pintype "passive"))
      (node (ref "P3") (pin "13") (pinfunction "13_13") (pintype "passive"))
      (node (ref "P3") (pin "15") (pinfunction "15_15") (pintype "passive"))
      (node (ref "P3") (pin "3") (pinfunction "3_3") (pintype "passive"))
      (node (ref "P3") (pin "5") (pinfunction "5_5") (pintype "passive"))
      (node (ref "P3") (pin "7") (pinfunction "7_7") (pintype "passive"))
      (node (ref "P3") (pin "9") (pinfunction "9_9") (pintype "passive"))
      (node (ref "P4") (pin "1") (pinfunction "1_1") (pintype "passive"))
      (node (ref "P4") (pin "11") (pinfunction "11_11") (pintype "passive"))
      (node (ref "P4") (pin "13") (pinfunction "13_13") (pintype "passive"))
      (node (ref "P4") (pin "15") (pinfunction "15_15") (pintype "passive"))
      (node (ref "P4") (pin "3") (pinfunction "3_3") (pintype "passive"))
      (node (ref "P4") (pin "5") (pinfunction "5_5") (pintype "passive"))
      (node (ref "P4") (pin "7") (pinfunction "7_7") (pintype "passive"))
      (node (ref "P4") (pin "9") (pinfunction "9_9") (pintype "passive"))
      (node (ref "P5") (pin "1") (pinfunction "1_1") (pintype "passive"))
      (node (ref "P5") (pin "11") (pinfunction "11_11") (pintype "passive"))
      (node (ref "P5") (pin "13") (pinfunction "13_13") (pintype "passive"))
      (node (ref "P5") (pin "15") (pinfunction "15_15") (pintype "passive"))
      (node (ref "P5") (pin "3") (pinfunction "3_3") (pintype "passive"))
      (node (ref "P5") (pin "5") (pinfunction "5_5") (pintype "passive"))
      (node (ref "P5") (pin "7") (pinfunction "7_7") (pintype "passive"))
      (node (ref "P5") (pin "9") (pinfunction "9_9") (pintype "passive"))
      (node (ref "R1") (pin "1") (pinfunction "1_1") (pintype "passive"))
      (node (ref "U1") (pin "45") (pinfunction "VBUS_45") (pintype "power_in"))
      (node (ref "U5") (pin "3") (pinfunction "IN_3") (pintype "power_in"))
      (node (ref "U6") (pin "1") (pinfunction "IN_1") (pintype "power_in"))
      (node (ref "U6") (pin "3") (pinfunction "EN_3") (pintype "input"))
    )
    (net (code "58") (name "0V9") (class "Default")
      (node (ref "C20") (pin "1") (pinfunction "1_1") (pintype "passive"))
      (node (ref "C21") (pin "1") (pinfunction "1_1") (pintype "passive"))
      (node (ref "R4") (pin "2") (pinfunction "2_2") (pintype "passive"))
      (node (ref "R5") (pin "1") (pinfunction "1_1") (pintype "passive"))
      (node (ref "U1") (pin "66") (pinfunction "DDRVREF_66") (pintype "power_in"))
    )
    (net (code "59") (name "1V8") (class "Default")
      (node (ref "C1") (pin "1") (pinfunction "1_1") (pintype "passive"))
      (node (ref "C107") (pin "1") (pinfunction "1_1") (pintype "passive"))
      (node (ref "C2") (pin "1") (pinfunction "1_1") (pintype "passive"))
      (node (ref "C24") (pin "1") (pinfunction "1_1") (pintype "passive"))
      (node (ref "C25") (pin "1") (pinfunction "1_1") (pintype "passive"))
      (node (ref "C26") (pin "1") (pinfunction "1_1") (pintype "passive"))
      (node (ref "C27") (pin "1") (pinfunction "1_1") (pintype "passive"))
      (node (ref "C28") (pin "1") (pinfunction "1_1") (pintype "passive"))
      (node (ref "C29") (pin "1") (pinfunction "1_1") (pintype "passive"))
      (node (ref "C3") (pin "1") (pinfunction "1_1") (pintype "passive"))
      (node (ref "C30") (pin "1") (pinfunction "1_1") (pintype "passive"))
      (node (ref "C31") (pin "1") (pinfunction "1_1") (pintype "passive"))
      (node (ref "C32") (pin "1") (pinfunction "1_1") (pintype "passive"))
      (node (ref "C33") (pin "1") (pinfunction "1_1") (pintype "passive"))
      (node (ref "C34") (pin "1") (pinfunction "1_1") (pintype "passive"))
      (node (ref "C35") (pin "1") (pinfunction "1_1") (pintype "passive"))
      (node (ref "C4") (pin "1") (pinfunction "1_1") (pintype "passive"))
      (node (ref "C5") (pin "1") (pinfunction "1_1") (pintype "passive"))
      (node (ref "R4") (pin "1") (pinfunction "1_1") (pintype "passive"))
      (node (ref "U1") (pin "116") (pinfunction "VDDCORE_116") (pintype "power_in"))
      (node (ref "U1") (pin "18") (pinfunction "VDDCORE_18") (pintype "power_in"))
      (node (ref "U1") (pin "39") (pinfunction "VDDCORE_39") (pintype "power_in"))
      (node (ref "U1") (pin "57") (pinfunction "VDDR1V8_57") (pintype "power_in"))
      (node (ref "U1") (pin "58") (pinfunction "VDDR1V8_58") (pintype "power_in"))
      (node (ref "U1") (pin "59") (pinfunction "VDDR1V8_59") (pintype "power_in"))
      (node (ref "U1") (pin "60") (pinfunction "VDDR1V8_60") (pintype "power_in"))
      (node (ref "U1") (pin "61") (pinfunction "VDDR1V8_61") (pintype "power_in"))
      (node (ref "U1") (pin "62") (pinfunction "VDDR1V8_62") (pintype "power_in"))
      (node (ref "U1") (pin "63") (pinfunction "VDDR1V8_63") (pintype "power_in"))
      (node (ref "U1") (pin "67") (pinfunction "VDDR1V8_67") (pintype "power_in"))
      (node (ref "U1") (pin "68") (pinfunction "VDDR1V8_68") (pintype "power_in"))
      (node (ref "U1") (pin "72") (pinfunction "VDDR1V8_72") (pintype "power_in"))
      (node (ref "U1") (pin "78") (pinfunction "VDDR1V8_78") (pintype "power_in"))
      (node (ref "U1") (pin "84") (pinfunction "VDDCORE_84") (pintype "power_in"))
      (node (ref "U6") (pin "5") (pinfunction "OUT_5") (pintype "power_in"))
    )
    (net (code "60") (name "3V3") (class "Default")
      (node (ref "C10") (pin "1") (pinfunction "1_1") (pintype "passive"))
      (node (ref "C101") (pin "2") (pinfunction "2_2") (pintype "passive"))
      (node (ref "C102") (pin "2") (pinfunction "2_2") (pintype "passive"))
      (node (ref "C11") (pin "1") (pinfunction "1_1") (pintype "passive"))
      (node (ref "C12") (pin "1") (pinfunction "1_1") (pintype "passive"))
      (node (ref "C13") (pin "1") (pinfunction "1_1") (pintype "passive"))
      (node (ref "C14") (pin "1") (pinfunction "1_1") (pintype "passive"))
      (node (ref "C15") (pin "1") (pinfunction "1_1") (pintype "passive"))
      (node (ref "C16") (pin "1") (pinfunction "1_1") (pintype "passive"))
      (node (ref "C17") (pin "1") (pinfunction "1_1") (pintype "passive"))
      (node (ref "C18") (pin "1") (pinfunction "1_1") (pintype "passive"))
      (node (ref "C19") (pin "1") (pinfunction "1_1") (pintype "passive"))
      (node (ref "C22") (pin "1") (pinfunction "1_1") (pintype "passive"))
      (node (ref "C23") (pin "1") (pinfunction "1_1") (pintype "passive"))
      (node (ref "C36") (pin "1") (pinfunction "1_1") (pintype "passive"))
      (node (ref "C37") (pin "1") (pinfunction "1_1") (pintype "passive"))
      (node (ref "C38") (pin "1") (pinfunction "1_1") (pintype "passive"))
      (node (ref "C6") (pin "1") (pinfunction "1_1") (pintype "passive"))
      (node (ref "C7") (pin "1") (pinfunction "1_1") (pintype "passive"))
      (node (ref "C8") (pin "1") (pinfunction "1_1") (pintype "passive"))
      (node (ref "C9") (pin "1") (pinfunction "1_1") (pintype "passive"))
      (node (ref "J8") (pin "4") (pinfunction "4_4") (pintype "passive"))
      (node (ref "L1") (pin "1") (pinfunction "1_1") (pintype "passive"))
      (node (ref "L1") (pin "2") (pinfunction "2_2") (pintype "passive"))
      (node (ref "L2") (pin "1") (pinfunction "1_1") (pintype "passive"))
      (node (ref "L2") (pin "2") (pinfunction "2_2") (pintype "passive"))
      (node (ref "R3") (pin "2") (pinfunction "2_2") (pintype "passive"))
      (node (ref "U1") (pin "102") (pinfunction "VDDIO_102") (pintype "power_in"))
      (node (ref "U1") (pin "117") (pinfunction "VDDIO_117") (pintype "power_in"))
      (node (ref "U1") (pin "124") (pinfunction "VDDIO_124") (pintype "power_in"))
      (node (ref "U1") (pin "155") (pinfunction "VDDIO_155") (pintype "power_in"))
      (node (ref "U1") (pin "156") (pinfunction "VDDIO_156") (pintype "power_in"))
      (node (ref "U1") (pin "165") (pinfunction "VDDIO_165") (pintype "power_in"))
      (node (ref "U1") (pin "166") (pinfunction "VBAT_166") (pintype "power_in"))
      (node (ref "U1") (pin "19") (pinfunction "VDDIO_19") (pintype "power_in"))
      (node (ref "U1") (pin "3") (pinfunction "AVDD_3") (pintype "power_in"))
      (node (ref "U1") (pin "38") (pinfunction "VDDIO_38") (pintype "power_in"))
      (node (ref "U1") (pin "4") (pinfunction "AVDD_4") (pintype "power_in"))
      (node (ref "U1") (pin "46") (pinfunction "VUSB3V3_46") (pintype "power_in"))
      (node (ref "U1") (pin "47") (pinfunction "VUSB3V3_47") (pintype "power_in"))
      (node (ref "U1") (pin "86") (pinfunction "VDDIO_86") (pintype "power_in"))
      (node (ref "U5") (pin "4") (pinfunction "OUT_4") (pintype "power_in"))
      (node (ref "Y1") (pin "1") (pinfunction "~{STBY}_1") (pintype "input"))
      (node (ref "Y1") (pin "4") (pinfunction "VDD_4") (pintype "power_in"))
      (node (ref "Y2") (pin "1") (pinfunction "Tri-state_1") (pintype "input"))
      (node (ref "Y2") (pin "4") (pinfunction "Vdd_4") (pintype "power_in"))
    )
    (net (code "61") (name "GND") (class "Default")
      (node (ref "C1") (pin "2") (pinfunction "2_2") (pintype "passive"))
      (node (ref "C10") (pin "2") (pinfunction "2_2") (pintype "passive"))
      (node (ref "C101") (pin "1") (pinfunction "1_1") (pintype "passive"))
      (node (ref "C102") (pin "1") (pinfunction "1_1") (pintype "passive"))
      (node (ref "C103") (pin "2") (pinfunction "2_2") (pintype "passive"))
      (node (ref "C104") (pin "2") (pinfunction "2_2") (pintype "passive"))
      (node (ref "C105") (pin "2") (pinfunction "2_2") (pintype "passive"))
      (node (ref "C106") (pin "2") (pinfunction "2_2") (pintype "passive"))
      (node (ref "C107") (pin "2") (pinfunction "2_2") (pintype "passive"))
      (node (ref "C11") (pin "2") (pinfunction "2_2") (pintype "passive"))
      (node (ref "C12") (pin "2") (pinfunction "2_2") (pintype "passive"))
      (node (ref "C13") (pin "2") (pinfunction "2_2") (pintype "passive"))
      (node (ref "C14") (pin "2") (pinfunction "2_2") (pintype "passive"))
      (node (ref "C15") (pin "2") (pinfunction "2_2") (pintype "passive"))
      (node (ref "C16") (pin "2") (pinfunction "2_2") (pintype "passive"))
      (node (ref "C17") (pin "2") (pinfunction "2_2") (pintype "passive"))
      (node (ref "C18") (pin "2") (pinfunction "2_2") (pintype "passive"))
      (node (ref "C19") (pin "2") (pinfunction "2_2") (pintype "passive"))
      (node (ref "C2") (pin "2") (pinfunction "2_2") (pintype "passive"))
      (node (ref "C20") (pin "2") (pinfunction "2_2") (pintype "passive"))
      (node (ref "C21") (pin "2") (pinfunction "2_2") (pintype "passive"))
      (node (ref "C22") (pin "2") (pinfunction "2_2") (pintype "passive"))
      (node (ref "C23") (pin "2") (pinfunction "2_2") (pintype "passive"))
      (node (ref "C24") (pin "2") (pinfunction "2_2") (pintype "passive"))
      (node (ref "C25") (pin "2") (pinfunction "2_2") (pintype "passive"))
      (node (ref "C26") (pin "2") (pinfunction "2_2") (pintype "passive"))
      (node (ref "C27") (pin "2") (pinfunction "2_2") (pintype "passive"))
      (node (ref "C28") (pin "2") (pinfunction "2_2") (pintype "passive"))
      (node (ref "C29") (pin "2") (pinfunction "2_2") (pintype "passive"))
      (node (ref "C3") (pin "2") (pinfunction "2_2") (pintype "passive"))
      (node (ref "C30") (pin "2") (pinfunction "2_2") (pintype "passive"))
      (node (ref "C31") (pin "2") (pinfunction "2_2") (pintype "passive"))
      (node (ref "C32") (pin "2") (pinfunction "2_2") (pintype "passive"))
      (node (ref "C33") (pin "2") (pinfunction "2_2") (pintype "passive"))
      (node (ref "C34") (pin "2") (pinfunction "2_2") (pintype "passive"))
      (node (ref "C35") (pin "2") (pinfunction "2_2") (pintype "passive"))
      (node (ref "C36") (pin "2") (pinfunction "2_2") (pintype "passive"))
      (node (ref "C37") (pin "2") (pinfunction "2_2") (pintype "passive"))
      (node (ref "C38") (pin "2") (pinfunction "2_2") (pintype "passive"))
      (node (ref "C4") (pin "2") (pinfunction "2_2") (pintype "passive"))
      (node (ref "C5") (pin "2") (pinfunction "2_2") (pintype "passive"))
      (node (ref "C6") (pin "2") (pinfunction "2_2") (pintype "passive"))
      (node (ref "C7") (pin "2") (pinfunction "2_2") (pintype "passive"))
      (node (ref "C8") (pin "2") (pinfunction "2_2") (pintype "passive"))
      (node (ref "C9") (pin "2") (pinfunction "2_2") (pintype "passive"))
      (node (ref "D1") (pin "1") (pinfunction "C_1") (pintype "passive"))
      (node (ref "J8") (pin "6") (pinfunction "6_6") (pintype "passive"))
      (node (ref "P1") (pin "3") (pinfunction "3_3") (pintype "passive"))
      (node (ref "P2") (pin "10") (pinfunction "10_10") (pintype "passive"))
      (node (ref "P2") (pin "12") (pinfunction "12_12") (pintype "passive"))
      (node (ref "P2") (pin "14") (pinfunction "14_14") (pintype "passive"))
      (node (ref "P2") (pin "16") (pinfunction "16_16") (pintype "passive"))
      (node (ref "P2") (pin "2") (pinfunction "2_2") (pintype "passive"))
      (node (ref "P2") (pin "4") (pinfunction "4_4") (pintype "passive"))
      (node (ref "P2") (pin "6") (pinfunction "6_6") (pintype "passive"))
      (node (ref "P2") (pin "8") (pinfunction "8_8") (pintype "passive"))
      (node (ref "P3") (pin "10") (pinfunction "10_10") (pintype "passive"))
      (node (ref "P3") (pin "12") (pinfunction "12_12") (pintype "passive"))
      (node (ref "P3") (pin "14") (pinfunction "14_14") (pintype "passive"))
      (node (ref "P3") (pin "16") (pinfunction "16_16") (pintype "passive"))
      (node (ref "P3") (pin "2") (pinfunction "2_2") (pintype "passive"))
      (node (ref "P3") (pin "4") (pinfunction "4_4") (pintype "passive"))
      (node (ref "P3") (pin "6") (pinfunction "6_6") (pintype "passive"))
      (node (ref "P3") (pin "8") (pinfunction "8_8") (pintype "passive"))
      (node (ref "P4") (pin "10") (pinfunction "10_10") (pintype "passive"))
      (node (ref "P4") (pin "12") (pinfunction "12_12") (pintype "passive"))
      (node (ref "P4") (pin "14") (pinfunction "14_14") (pintype "passive"))
      (node (ref "P4") (pin "16") (pinfunction "16_16") (pintype "passive"))
      (node (ref "P4") (pin "2") (pinfunction "2_2") (pintype "passive"))
      (node (ref "P4") (pin "4") (pinfunction "4_4") (pintype "passive"))
      (node (ref "P4") (pin "6") (pinfunction "6_6") (pintype "passive"))
      (node (ref "P4") (pin "8") (pinfunction "8_8") (pintype "passive"))
      (node (ref "P5") (pin "10") (pinfunction "10_10") (pintype "passive"))
      (node (ref "P5") (pin "12") (pinfunction "12_12") (pintype "passive"))
      (node (ref "P5") (pin "14") (pinfunction "14_14") (pintype "passive"))
      (node (ref "P5") (pin "16") (pinfunction "16_16") (pintype "passive"))
      (node (ref "P5") (pin "2") (pinfunction "2_2") (pintype "passive"))
      (node (ref "P5") (pin "4") (pinfunction "4_4") (pintype "passive"))
      (node (ref "P5") (pin "6") (pinfunction "6_6") (pintype "passive"))
      (node (ref "P5") (pin "8") (pinfunction "8_8") (pintype "passive"))
      (node (ref "R5") (pin "2") (pinfunction "2_2") (pintype "passive"))
      (node (ref "SW1") (pin "3") (pinfunction "3_3") (pintype "passive"))
      (node (ref "SW1") (pin "4") (pinfunction "4_4") (pintype "passive"))
      (node (ref "U1") (pin "103") (pinfunction "VSS_103") (pintype "passive"))
      (node (ref "U1") (pin "115") (pinfunction "VSS_115") (pintype "passive"))
      (node (ref "U1") (pin "122") (pinfunction "VSS_122") (pintype "passive"))
      (node (ref "U1") (pin "123") (pinfunction "VSS_123") (pintype "passive"))
      (node (ref "U1") (pin "153") (pinfunction "VSS_153") (pintype "passive"))
      (node (ref "U1") (pin "154") (pinfunction "VSS_154") (pintype "passive"))
      (node (ref "U1") (pin "21") (pinfunction "VSS_21") (pintype "passive"))
      (node (ref "U1") (pin "22") (pinfunction "VSS_22") (pintype "passive"))
      (node (ref "U1") (pin "29") (pinfunction "VSS_29") (pintype "passive"))
      (node (ref "U1") (pin "37") (pinfunction "VSS_37") (pintype "passive"))
      (node (ref "U1") (pin "48") (pinfunction "VSS_48") (pintype "passive"))
      (node (ref "U1") (pin "49") (pinfunction "VSS_49") (pintype "passive"))
      (node (ref "U1") (pin "5") (pinfunction "AVSS_5") (pintype "passive"))
      (node (ref "U1") (pin "6") (pinfunction "AVSS_6") (pintype "passive"))
      (node (ref "U1") (pin "83") (pinfunction "VSS_83") (pintype "passive"))
      (node (ref "U1") (pin "87") (pinfunction "VSS_87") (pintype "passive"))
      (node (ref "U1") (pin "94") (pinfunction "VSS_94") (pintype "passive"))
      (node (ref "U1") (pin "EPAD") (pinfunction "VSS1V8_EPAD") (pintype "passive"))
      (node (ref "U5") (pin "1") (pinfunction "GND_1") (pintype "power_in"))
      (node (ref "U6") (pin "2") (pinfunction "GND_2") (pintype "power_in"))
      (node (ref "Y1") (pin "2") (pinfunction "GND/Case_2") (pintype "power_in"))
      (node (ref "Y2") (pin "2") (pinfunction "GND_2") (pintype "power_in"))
    )
    (net (code "62") (name "Net-(C103-Pad1)") (class "Default")
      (node (ref "C103") (pin "1") (pinfunction "1_1") (pintype "passive"))
      (node (ref "R2") (pin "2") (pinfunction "2_2") (pintype "passive"))
      (node (ref "R3") (pin "1") (pinfunction "1_1") (pintype "passive"))
      (node (ref "SW1") (pin "1") (pinfunction "1_1") (pintype "passive"))
      (node (ref "SW1") (pin "2") (pinfunction "2_2") (pintype "passive"))
    )
    (net (code "63") (name "Net-(C105-Pad1)") (class "Default")
      (node (ref "C105") (pin "1") (pinfunction "1_1") (pintype "passive"))
      (node (ref "U5") (pin "2") (pinfunction "OUT_2") (pintype "power_in"))
    )
    (net (code "64") (name "Net-(D1-A)") (class "Default")
      (node (ref "D1") (pin "2") (pinfunction "A_2") (pintype "passive"))
      (node (ref "R1") (pin "2") (pinfunction "2_2") (pintype "passive"))
    )
    (net (code "65") (name "unconnected-(J1-Pad3)") (class "Default")
      (node (ref "J1") (pin "3") (pinfunction "3_3") (pintype "passive"))
    )
    (net (code "66") (name "unconnected-(J1-Pad4)") (class "Default")
      (node (ref "J1") (pin "4") (pinfunction "4_4") (pintype "passive"))
    )
    (net (code "67") (name "unconnected-(J1-Pad5)") (class "Default")
      (node (ref "J1") (pin "5") (pinfunction "5_5") (pintype "passive"))
    )
    (net (code "68") (name "unconnected-(J1-Pad6)") (class "Default")
      (node (ref "J1") (pin "6") (pinfunction "6_6") (pintype "passive"))
    )
    (net (code "69") (name "unconnected-(J1-Pad7)") (class "Default")
      (node (ref "J1") (pin "7") (pinfunction "7_7") (pintype "passive"))
    )
    (net (code "70") (name "unconnected-(J1-Pad8)") (class "Default")
      (node (ref "J1") (pin "8") (pinfunction "8_8") (pintype "passive"))
    )
    (net (code "71") (name "unconnected-(J1-Pad9)") (class "Default")
      (node (ref "J1") (pin "9") (pinfunction "9_9") (pintype "passive"))
    )
    (net (code "72") (name "unconnected-(J1-Pad10)") (class "Default")
      (node (ref "J1") (pin "10") (pinfunction "10_10") (pintype "passive"))
    )
    (net (code "73") (name "unconnected-(J1-Pad11)") (class "Default")
      (node (ref "J1") (pin "11") (pinfunction "11_11") (pintype "passive"))
    )
    (net (code "74") (name "unconnected-(J1-Pad12)") (class "Default")
      (node (ref "J1") (pin "12") (pinfunction "12_12") (pintype "passive"))
    )
    (net (code "75") (name "unconnected-(J1-Pad13)") (class "Default")
      (node (ref "J1") (pin "13") (pinfunction "13_13") (pintype "passive"))
    )
    (net (code "76") (name "unconnected-(J1-Pad14)") (class "Default")
      (node (ref "J1") (pin "14") (pinfunction "14_14") (pintype "passive"))
    )
    (net (code "77") (name "unconnected-(J1-Pad15)") (class "Default")
      (node (ref "J1") (pin "15") (pinfunction "15_15") (pintype "passive"))
    )
    (net (code "78") (name "unconnected-(J1-Pad16)") (class "Default")
      (node (ref "J1") (pin "16") (pinfunction "16_16") (pintype "passive"))
    )
    (net (code "79") (name "unconnected-(J2-Pad8)") (class "Default")
      (node (ref "J2") (pin "8") (pinfunction "8_8") (pintype "passive"))
    )
    (net (code "80") (name "unconnected-(J2-Pad10)") (class "Default")
      (node (ref "J2") (pin "10") (pinfunction "10_10") (pintype "passive"))
    )
    (net (code "81") (name "unconnected-(J2-Pad12)") (class "Default")
      (node (ref "J2") (pin "12") (pinfunction "12_12") (pintype "passive"))
    )
    (net (code "82") (name "unconnected-(J2-Pad14)") (class "Default")
      (node (ref "J2") (pin "14") (pinfunction "14_14") (pintype "passive"))
    )
    (net (code "83") (name "unconnected-(J2-Pad16)") (class "Default")
      (node (ref "J2") (pin "16") (pinfunction "16_16") (pintype "passive"))
    )
    (net (code "84") (name "unconnected-(J3-Pad12)") (class "Default")
      (node (ref "J3") (pin "12") (pinfunction "12_12") (pintype "passive+no_connect"))
    )
    (net (code "85") (name "unconnected-(J3-Pad14)") (class "Default")
      (node (ref "J3") (pin "14") (pinfunction "14_14") (pintype "passive+no_connect"))
    )
    (net (code "86") (name "unconnected-(J3-Pad15)") (class "Default")
      (node (ref "J3") (pin "15") (pinfunction "15_15") (pintype "passive+no_connect"))
    )
    (net (code "87") (name "unconnected-(J3-Pad16)") (class "Default")
      (node (ref "J3") (pin "16") (pinfunction "16_16") (pintype "passive+no_connect"))
    )
    (net (code "88") (name "unconnected-(J4-Pad4)") (class "Default")
      (node (ref "J4") (pin "4") (pinfunction "4_4") (pintype "passive"))
    )
    (net (code "89") (name "unconnected-(J4-Pad6)") (class "Default")
      (node (ref "J4") (pin "6") (pinfunction "6_6") (pintype "passive"))
    )
    (net (code "90") (name "unconnected-(J5-Pad11)") (class "Default")
      (node (ref "J5") (pin "11") (pinfunction "11_11") (pintype "passive"))
    )
    (net (code "91") (name "unconnected-(J5-Pad12)") (class "Default")
      (node (ref "J5") (pin "12") (pinfunction "12_12") (pintype "passive"))
    )
    (net (code "92") (name "unconnected-(J5-Pad13)") (class "Default")
      (node (ref "J5") (pin "13") (pinfunction "13_13") (pintype "passive"))
    )
    (net (code "93") (name "unconnected-(J5-Pad15)") (class "Default")
      (node (ref "J5") (pin "15") (pinfunction "15_15") (pintype "passive"))
    )
    (net (code "94") (name "unconnected-(J8-Pad1)") (class "Default")
      (node (ref "J8") (pin "1") (pinfunction "1_1") (pintype "passive"))
    )
    (net (code "95") (name "unconnected-(J8-Pad3)") (class "Default")
      (node (ref "J8") (pin "3") (pinfunction "3_3") (pintype "passive"))
    )
    (net (code "96") (name "unconnected-(J8-Pad5)") (class "Default")
      (node (ref "J8") (pin "5") (pinfunction "5_5") (pintype "passive"))
    )
    (net (code "97") (name "unconnected-(J8-Pad7)") (class "Default")
      (node (ref "J8") (pin "7") (pinfunction "7_7") (pintype "passive"))
    )
    (net (code "98") (name "unconnected-(J8-Pad9)") (class "Default")
      (node (ref "J8") (pin "9") (pinfunction "9_9") (pintype "passive"))
    )
    (net (code "99") (name "unconnected-(J8-Pad11)") (class "Default")
      (node (ref "J8") (pin "11") (pinfunction "11_11") (pintype "passive"))
    )
    (net (code "100") (name "unconnected-(J8-Pad12)") (class "Default")
      (node (ref "J8") (pin "12") (pinfunction "12_12") (pintype "passive+no_connect"))
    )
    (net (code "101") (name "unconnected-(J8-Pad13)") (class "Default")
      (node (ref "J8") (pin "13") (pinfunction "13_13") (pintype "passive"))
    )
    (net (code "102") (name "unconnected-(J8-Pad14)") (class "Default")
      (node (ref "J8") (pin "14") (pinfunction "14_14") (pintype "passive+no_connect"))
    )
    (net (code "103") (name "unconnected-(J8-Pad15)") (class "Default")
      (node (ref "J8") (pin "15") (pinfunction "15_15") (pintype "passive"))
    )
    (net (code "104") (name "unconnected-(J8-Pad16)") (class "Default")
      (node (ref "J8") (pin "16") (pinfunction "16_16") (pintype "passive+no_connect"))
    )
    (net (code "105") (name "unconnected-(P1-Pad2)") (class "Default")
      (node (ref "P1") (pin "2") (pinfunction "2_2") (pintype "passive+no_connect"))
    )
    (net (code "106") (name "unconnected-(U1A-*SDWP{slash}EBIRP{slash}RH2-Pad141)") (class "Default")
      (node (ref "U1") (pin "141") (pinfunction "*SDWP/EBIRP/RH2_141") (pintype "bidirectional+no_connect"))
    )
    (net (code "107") (name "unconnected-(U1A-D+-Pad51)") (class "Default")
      (node (ref "U1") (pin "51") (pinfunction "D+_51") (pintype "bidirectional+no_connect"))
    )
    (net (code "108") (name "unconnected-(U1A-D--Pad50)") (class "Default")
      (node (ref "U1") (pin "50") (pinfunction "D-_50") (pintype "bidirectional+no_connect"))
    )
    (net (code "109") (name "unconnected-(U1A-EBIA0{slash}PMA0{slash}RJ15-Pad142)") (class "Default")
      (node (ref "U1") (pin "142") (pinfunction "EBIA0/PMA0/RJ15_142") (pintype "bidirectional"))
    )
    (net (code "110") (name "unconnected-(U1A-EBIA1{slash}AN38{slash}PMA1{slash}RK1-Pad136)") (class "Default")
      (node (ref "U1") (pin "136") (pinfunction "EBIA1/AN38/PMA1/RK1_136") (pintype "bidirectional"))
    )
    (net (code "111") (name "unconnected-(U1A-EBIA2{slash}AN23{slash}C2INC{slash}RPG9{slash}PMA2{slash}RG9-Pad33)") (class "Default")
      (node (ref "U1") (pin "33") (pinfunction "EBIA2/AN23/C2INC/RPG9/PMA2/RG9_33") (pintype "bidirectional"))
    )
    (net (code "112") (name "unconnected-(U1A-EBIA3{slash}AN11{slash}PMA3{slash}RK2-Pad135)") (class "Default")
      (node (ref "U1") (pin "135") (pinfunction "EBIA3/AN11/PMA3/RK2_135") (pintype "bidirectional"))
    )
    (net (code "113") (name "unconnected-(U1A-EBIA4{slash}AN36{slash}PMA4{slash}RH7-Pad139)") (class "Default")
      (node (ref "U1") (pin "139") (pinfunction "EBIA4/AN36/PMA4/RH7_139") (pintype "bidirectional"))
    )
    (net (code "114") (name "unconnected-(U1A-EBID0{slash}PMD0{slash}RE0-Pad40)") (class "Default")
      (node (ref "U1") (pin "40") (pinfunction "EBID0/PMD0/RE0_40") (pintype "bidirectional"))
    )
    (net (code "115") (name "unconnected-(U1A-EBID1{slash}AN39{slash}PMD1{slash}RE1-Pad36)") (class "Default")
      (node (ref "U1") (pin "36") (pinfunction "EBID1/AN39/PMD1/RE1_36") (pintype "bidirectional"))
    )
    (net (code "116") (name "unconnected-(U1A-EBID2{slash}PMD2{slash}RE2-Pad99)") (class "Default")
      (node (ref "U1") (pin "99") (pinfunction "EBID2/PMD2/RE2_99") (pintype "bidirectional"))
    )
    (net (code "117") (name "unconnected-(U1A-EBID3{slash}RPE3{slash}PMD3{slash}RE3-Pad98)") (class "Default")
      (node (ref "U1") (pin "98") (pinfunction "EBID3/RPE3/PMD3/RE3_98") (pintype "bidirectional"))
    )
    (net (code "118") (name "unconnected-(U1A-EBID4{slash}AN18{slash}PMD4{slash}RE4-Pad43)") (class "Default")
      (node (ref "U1") (pin "43") (pinfunction "EBID4/AN18/PMD4/RE4_43") (pintype "bidirectional"))
    )
    (net (code "119") (name "unconnected-(U1A-EBID6{slash}AN16{slash}PMD6{slash}RE6-Pad23)") (class "Default")
      (node (ref "U1") (pin "23") (pinfunction "EBID6/AN16/PMD6/RE6_23") (pintype "bidirectional"))
    )
    (net (code "120") (name "unconnected-(U1A-EBID7{slash}AN15{slash}PMD7{slash}RE7-Pad24)") (class "Default")
      (node (ref "U1") (pin "24") (pinfunction "EBID7/AN15/PMD7/RE7_24") (pintype "bidirectional"))
    )
    (net (code "121") (name "unconnected-(U1A-EBIRDY2{slash}AN37{slash}RH11-Pad138)") (class "Default")
      (node (ref "U1") (pin "138") (pinfunction "EBIRDY2/AN37/RH11_138") (pintype "bidirectional"))
    )
    (net (code "122") (name "unconnected-(U1A-EBIRDY3{slash}AN32{slash}RJ2-Pad152)") (class "Default")
      (node (ref "U1") (pin "152") (pinfunction "EBIRDY3/AN32/RJ2_152") (pintype "bidirectional"))
    )
    (net (code "123") (name "unconnected-(U1A-ECOL{slash}RH10-Pad106)") (class "Default")
      (node (ref "U1") (pin "106") (pinfunction "ECOL/RH10_106") (pintype "bidirectional"))
    )
    (net (code "124") (name "unconnected-(U1A-ECRS{slash}RH12-Pad105)") (class "Default")
      (node (ref "U1") (pin "105") (pinfunction "ECRS/RH12_105") (pintype "bidirectional"))
    )
    (net (code "125") (name "unconnected-(U1A-EMDIO{slash}RJ1-Pad114)") (class "Default")
      (node (ref "U1") (pin "114") (pinfunction "EMDIO/RJ1_114") (pintype "bidirectional"))
    )
    (net (code "126") (name "unconnected-(U1A-ERXCLK{slash}EREFCLK{slash}RJ11-Pad111)") (class "Default")
      (node (ref "U1") (pin "111") (pinfunction "ERXCLK/EREFCLK/RJ11_111") (pintype "bidirectional"))
    )
    (net (code "127") (name "unconnected-(U1A-ERXD0{slash}RH8-Pad108)") (class "Default")
      (node (ref "U1") (pin "108") (pinfunction "ERXD0/RH8_108") (pintype "bidirectional"))
    )
    (net (code "128") (name "unconnected-(U1A-ERXD1{slash}RH5-Pad100)") (class "Default")
      (node (ref "U1") (pin "100") (pinfunction "ERXD1/RH5_100") (pintype "bidirectional"))
    )
    (net (code "129") (name "unconnected-(U1A-ERXD2{slash}RH6-Pad101)") (class "Default")
      (node (ref "U1") (pin "101") (pinfunction "ERXD2/RH6_101") (pintype "bidirectional"))
    )
    (net (code "130") (name "unconnected-(U1A-ERXD3{slash}RH9-Pad107)") (class "Default")
      (node (ref "U1") (pin "107") (pinfunction "ERXD3/RH9_107") (pintype "bidirectional"))
    )
    (net (code "131") (name "unconnected-(U1A-ERXDV{slash}ECRSDV{slash}RH13-Pad104)") (class "Default")
      (node (ref "U1") (pin "104") (pinfunction "ERXDV/ECRSDV/RH13_104") (pintype "bidirectional"))
    )
    (net (code "132") (name "unconnected-(U1A-ETXD0{slash}RJ8-Pad113)") (class "Default")
      (node (ref "U1") (pin "113") (pinfunction "ETXD0/RJ8_113") (pintype "bidirectional"))
    )
    (net (code "133") (name "unconnected-(U1A-ETXD1{slash}RJ9-Pad112)") (class "Default")
      (node (ref "U1") (pin "112") (pinfunction "ETXD1/RJ9_112") (pintype "bidirectional"))
    )
    (net (code "134") (name "unconnected-(U1A-ETXD2{slash}RH0-Pad110)") (class "Default")
      (node (ref "U1") (pin "110") (pinfunction "ETXD2/RH0_110") (pintype "bidirectional"))
    )
    (net (code "135") (name "unconnected-(U1A-ETXD3{slash}RH1-Pad109)") (class "Default")
      (node (ref "U1") (pin "109") (pinfunction "ETXD3/RH1_109") (pintype "bidirectional"))
    )
    (net (code "136") (name "unconnected-(U1A-ETXERR{slash}RJ0-Pad118)") (class "Default")
      (node (ref "U1") (pin "118") (pinfunction "ETXERR/RJ0_118") (pintype "bidirectional"))
    )
    (net (code "137") (name "unconnected-(U1A-GCLK{slash}EBICS2{slash}RJ6-Pad148)") (class "Default")
      (node (ref "U1") (pin "148") (pinfunction "GCLK/EBICS2/RJ6_148") (pintype "bidirectional"))
    )
    (net (code "138") (name "unconnected-(U1A-INT0{slash}RH14-Pad42)") (class "Default")
      (node (ref "U1") (pin "42") (pinfunction "INT0/RH14_42") (pintype "bidirectional+no_connect"))
    )
    (net (code "139") (name "unconnected-(U1B-GD0{slash}EBID13{slash}PMD13{slash}RJ13-Pad144)") (class "Default")
      (node (ref "U1") (pin "144") (pinfunction "GD0/EBID13/PMD13/RJ13_144") (pintype "bidirectional"))
    )
    (net (code "140") (name "unconnected-(U1B-GD1{slash}EBID14{slash}PMD14{slash}RA4-Pad127)") (class "Default")
      (node (ref "U1") (pin "127") (pinfunction "GD1/EBID14/PMD14/RA4_127") (pintype "bidirectional"))
    )
    (net (code "141") (name "unconnected-(U1B-GD2{slash}EBID15{slash}RPD9{slash}PMD15{slash}RD9-Pad76)") (class "Default")
      (node (ref "U1") (pin "76") (pinfunction "GD2/EBID15/RPD9/PMD15/RD9_76") (pintype "bidirectional"))
    )
    (net (code "142") (name "unconnected-(U1B-GD7{slash}EBIA12{slash}RPD12{slash}PMA12{slash}RD12-Pad80)") (class "Default")
      (node (ref "U1") (pin "80") (pinfunction "GD7/EBIA12/RPD12/PMA12/RD12_80") (pintype "bidirectional"))
    )
    (net (code "143") (name "unconnected-(U1B-GD8{slash}EBID11{slash}PMD11{slash}RJ14-Pad143)") (class "Default")
      (node (ref "U1") (pin "143") (pinfunction "GD8/EBID11/PMD11/RJ14_143") (pintype "bidirectional"))
    )
    (net (code "144") (name "unconnected-(U1B-GD9{slash}EBIBS0{slash}RJ12-Pad145)") (class "Default")
      (node (ref "U1") (pin "145") (pinfunction "GD9/EBIBS0/RJ12_145") (pintype "bidirectional"))
    )
    (net (code "145") (name "unconnected-(U1B-GD10{slash}EBIA14{slash}RPD2{slash}PMA14{slash}PMCS1{slash}RD2-Pad74)") (class "Default")
      (node (ref "U1") (pin "74") (pinfunction "GD10/EBIA14/RPD2/PMA14/PMCS1/RD2_74") (pintype "bidirectional"))
    )
    (net (code "146") (name "unconnected-(U1B-GD11{slash}EBIA15{slash}RPD3{slash}PMA15{slash}PMCS2{slash}RD3-Pad75)") (class "Default")
      (node (ref "U1") (pin "75") (pinfunction "GD11/EBIA15/RPD3/PMA15/PMCS2/RD3_75") (pintype "bidirectional"))
    )
    (net (code "147") (name "unconnected-(U1B-GD12{slash}EBIA17{slash}RK3-Pad134)") (class "Default")
      (node (ref "U1") (pin "134") (pinfunction "GD12/EBIA17/RK3_134") (pintype "bidirectional"))
    )
    (net (code "148") (name "unconnected-(U1B-GD13{slash}EBIA18{slash}RK4-Pad133)") (class "Default")
      (node (ref "U1") (pin "133") (pinfunction "GD13/EBIA18/RK4_133") (pintype "bidirectional"))
    )
    (net (code "149") (name "unconnected-(U1B-GD14{slash}EBIA19{slash}RK5-Pad132)") (class "Default")
      (node (ref "U1") (pin "132") (pinfunction "GD14/EBIA19/RK5_132") (pintype "bidirectional"))
    )
    (net (code "150") (name "unconnected-(U1B-GD15{slash}EBIA20{slash}RK6-Pad131)") (class "Default")
      (node (ref "U1") (pin "131") (pinfunction "GD15/EBIA20/RK6_131") (pintype "bidirectional"))
    )
    (net (code "151") (name "unconnected-(U1B-GD18{slash}EBIBS1{slash}RJ10-Pad146)") (class "Default")
      (node (ref "U1") (pin "146") (pinfunction "GD18/EBIBS1/RJ10_146") (pintype "bidirectional"))
    )
    (net (code "152") (name "unconnected-(U1B-GD19{slash}EBIA21{slash}RK7-Pad130)") (class "Default")
      (node (ref "U1") (pin "130") (pinfunction "GD19/EBIA21/RK7_130") (pintype "bidirectional"))
    )
    (net (code "153") (name "unconnected-(U1B-GD20{slash}EBIA22{slash}RJ3-Pad151)") (class "Default")
      (node (ref "U1") (pin "151") (pinfunction "GD20/EBIA22/RJ3_151") (pintype "bidirectional"))
    )
    (net (code "154") (name "unconnected-(U1B-GD21{slash}EBIA23{slash}RH15-Pad92)") (class "Default")
      (node (ref "U1") (pin "92") (pinfunction "GD21/EBIA23/RH15_92") (pintype "bidirectional"))
    )
    (net (code "155") (name "unconnected-(U1B-GD22{slash}EBIA13{slash}PMA13{slash}RD13-Pad81)") (class "Default")
      (node (ref "U1") (pin "81") (pinfunction "GD22/EBIA13/PMA13/RD13_81") (pintype "bidirectional"))
    )
    (net (code "156") (name "unconnected-(U1B-GD23{slash}EBIA16{slash}RK0-Pad137)") (class "Default")
      (node (ref "U1") (pin "137") (pinfunction "GD23/EBIA16/RK0_137") (pintype "bidirectional"))
    )
    (net (code "157") (name "unconnected-(U1B-GEN{slash}EBICS3{slash}RJ7-Pad147)") (class "Default")
      (node (ref "U1") (pin "147") (pinfunction "GEN/EBICS3/RJ7_147") (pintype "bidirectional"))
    )
    (net (code "158") (name "unconnected-(U1B-HSYNC{slash}EBICS1{slash}RJ5-Pad149)") (class "Default")
      (node (ref "U1") (pin "149") (pinfunction "HSYNC/EBICS1/RJ5_149") (pintype "bidirectional"))
    )
    (net (code "159") (name "unconnected-(U1B-OSC2{slash}CLKO{slash}RC15-Pad163)") (class "Default")
      (node (ref "U1") (pin "163") (pinfunction "OSC2/CLKO/RC15_163") (pintype "bidirectional"))
    )
    (net (code "160") (name "unconnected-(U1B-SCK1{slash}RD1-Pad73)") (class "Default")
      (node (ref "U1") (pin "73") (pinfunction "SCK1/RD1_73") (pintype "bidirectional"))
    )
    (net (code "161") (name "unconnected-(U1B-SCK4{slash}RD10-Pad77)") (class "Default")
      (node (ref "U1") (pin "77") (pinfunction "SCK4/RD10_77") (pintype "bidirectional"))
    )
    (net (code "162") (name "unconnected-(U1B-SDCMD{slash}SQICS0{slash}RPD4{slash}RD4-Pad70)") (class "Default")
      (node (ref "U1") (pin "70") (pinfunction "SDCMD/SQICS0/RPD4/RD4_70") (pintype "bidirectional"))
    )
    (net (code "163") (name "unconnected-(U1B-SQICS1{slash}RPD5{slash}RD5-Pad71)") (class "Default")
      (node (ref "U1") (pin "71") (pinfunction "SQICS1/RPD5/RD5_71") (pintype "bidirectional"))
    )
    (net (code "164") (name "unconnected-(U1B-TCK{slash}AN24{slash}RA1-Pad160)") (class "Default")
      (node (ref "U1") (pin "160") (pinfunction "TCK/AN24/RA1_160") (pintype "bidirectional"))
    )
    (net (code "165") (name "unconnected-(U1B-TDI{slash}AN17{slash}SCK5{slash}RF13-Pad28)") (class "Default")
      (node (ref "U1") (pin "28") (pinfunction "TDI/AN17/SCK5/RF13_28") (pintype "bidirectional"))
    )
    (net (code "166") (name "unconnected-(U1B-TMS{slash}*SDCD{slash}RA0-Pad53)") (class "Default")
      (node (ref "U1") (pin "53") (pinfunction "TMS/*SDCD/RA0_53") (pintype "bidirectional"))
    )
    (net (code "167") (name "unconnected-(U1B-TRCLK{slash}SDCK{slash}SQICLK{slash}RA6-Pad54)") (class "Default")
      (node (ref "U1") (pin "54") (pinfunction "TRCLK/SDCK/SQICLK/RA6_54") (pintype "bidirectional"))
    )
    (net (code "168") (name "unconnected-(U1B-TRD0{slash}SDDATA0{slash}SQID0{slash}RG13-Pad64)") (class "Default")
      (node (ref "U1") (pin "64") (pinfunction "TRD0/SDDATA0/SQID0/RG13_64") (pintype "bidirectional"))
    )
    (net (code "169") (name "unconnected-(U1B-TRD1{slash}SDDATA1{slash}SQID1{slash}RG12-Pad56)") (class "Default")
      (node (ref "U1") (pin "56") (pinfunction "TRD1/SDDATA1/SQID1/RG12_56") (pintype "bidirectional"))
    )
    (net (code "170") (name "unconnected-(U1B-TRD2{slash}SDDATA2{slash}SQID2{slash}RG14-Pad65)") (class "Default")
      (node (ref "U1") (pin "65") (pinfunction "TRD2/SDDATA2/SQID2/RG14_65") (pintype "bidirectional"))
    )
    (net (code "171") (name "unconnected-(U1B-TRD3{slash}SDDATA3{slash}SQID3{slash}RA7-Pad55)") (class "Default")
      (node (ref "U1") (pin "55") (pinfunction "TRD3/SDDATA3/SQID3/RA7_55") (pintype "bidirectional"))
    )
    (net (code "172") (name "unconnected-(U1B-USBID-Pad52)") (class "Default")
      (node (ref "U1") (pin "52") (pinfunction "USBID_52") (pintype "bidirectional+no_connect"))
    )
    (net (code "173") (name "unconnected-(U1B-VSYNC{slash}EBICS0{slash}RJ4-Pad150)") (class "Default")
      (node (ref "U1") (pin "150") (pinfunction "VSYNC/EBICS0/RJ4_150") (pintype "bidirectional"))
    )
    (net (code "174") (name "unconnected-(U1D-No_Connect-Pad20)") (class "Default")
      (node (ref "U1") (pin "20") (pinfunction "No_Connect_20") (pintype "passive+no_connect"))
    )
    (net (code "175") (name "unconnected-(U1D-No_Connect-Pad44)") (class "Default")
      (node (ref "U1") (pin "44") (pinfunction "No_Connect_44") (pintype "passive+no_connect"))
    )
    (net (code "176") (name "unconnected-(U1D-No_Connect-Pad88)") (class "Default")
      (node (ref "U1") (pin "88") (pinfunction "No_Connect_88") (pintype "passive+no_connect"))
    )
    (net (code "177") (name "unconnected-(U1D-No_Connect-Pad176)") (class "Default")
      (node (ref "U1") (pin "176") (pinfunction "No_Connect_176") (pintype "passive+no_connect"))
    )
    (net (code "178") (name "unconnected-(U6-NC-Pad4)") (class "Default")
      (node (ref "U6") (pin "4") (pinfunction "NC_4") (pintype "passive+no_connect"))
    )
  )
)
